# DanielDist_board_1_17.net
KiCad netlist of a schematic drawn in EAGLE
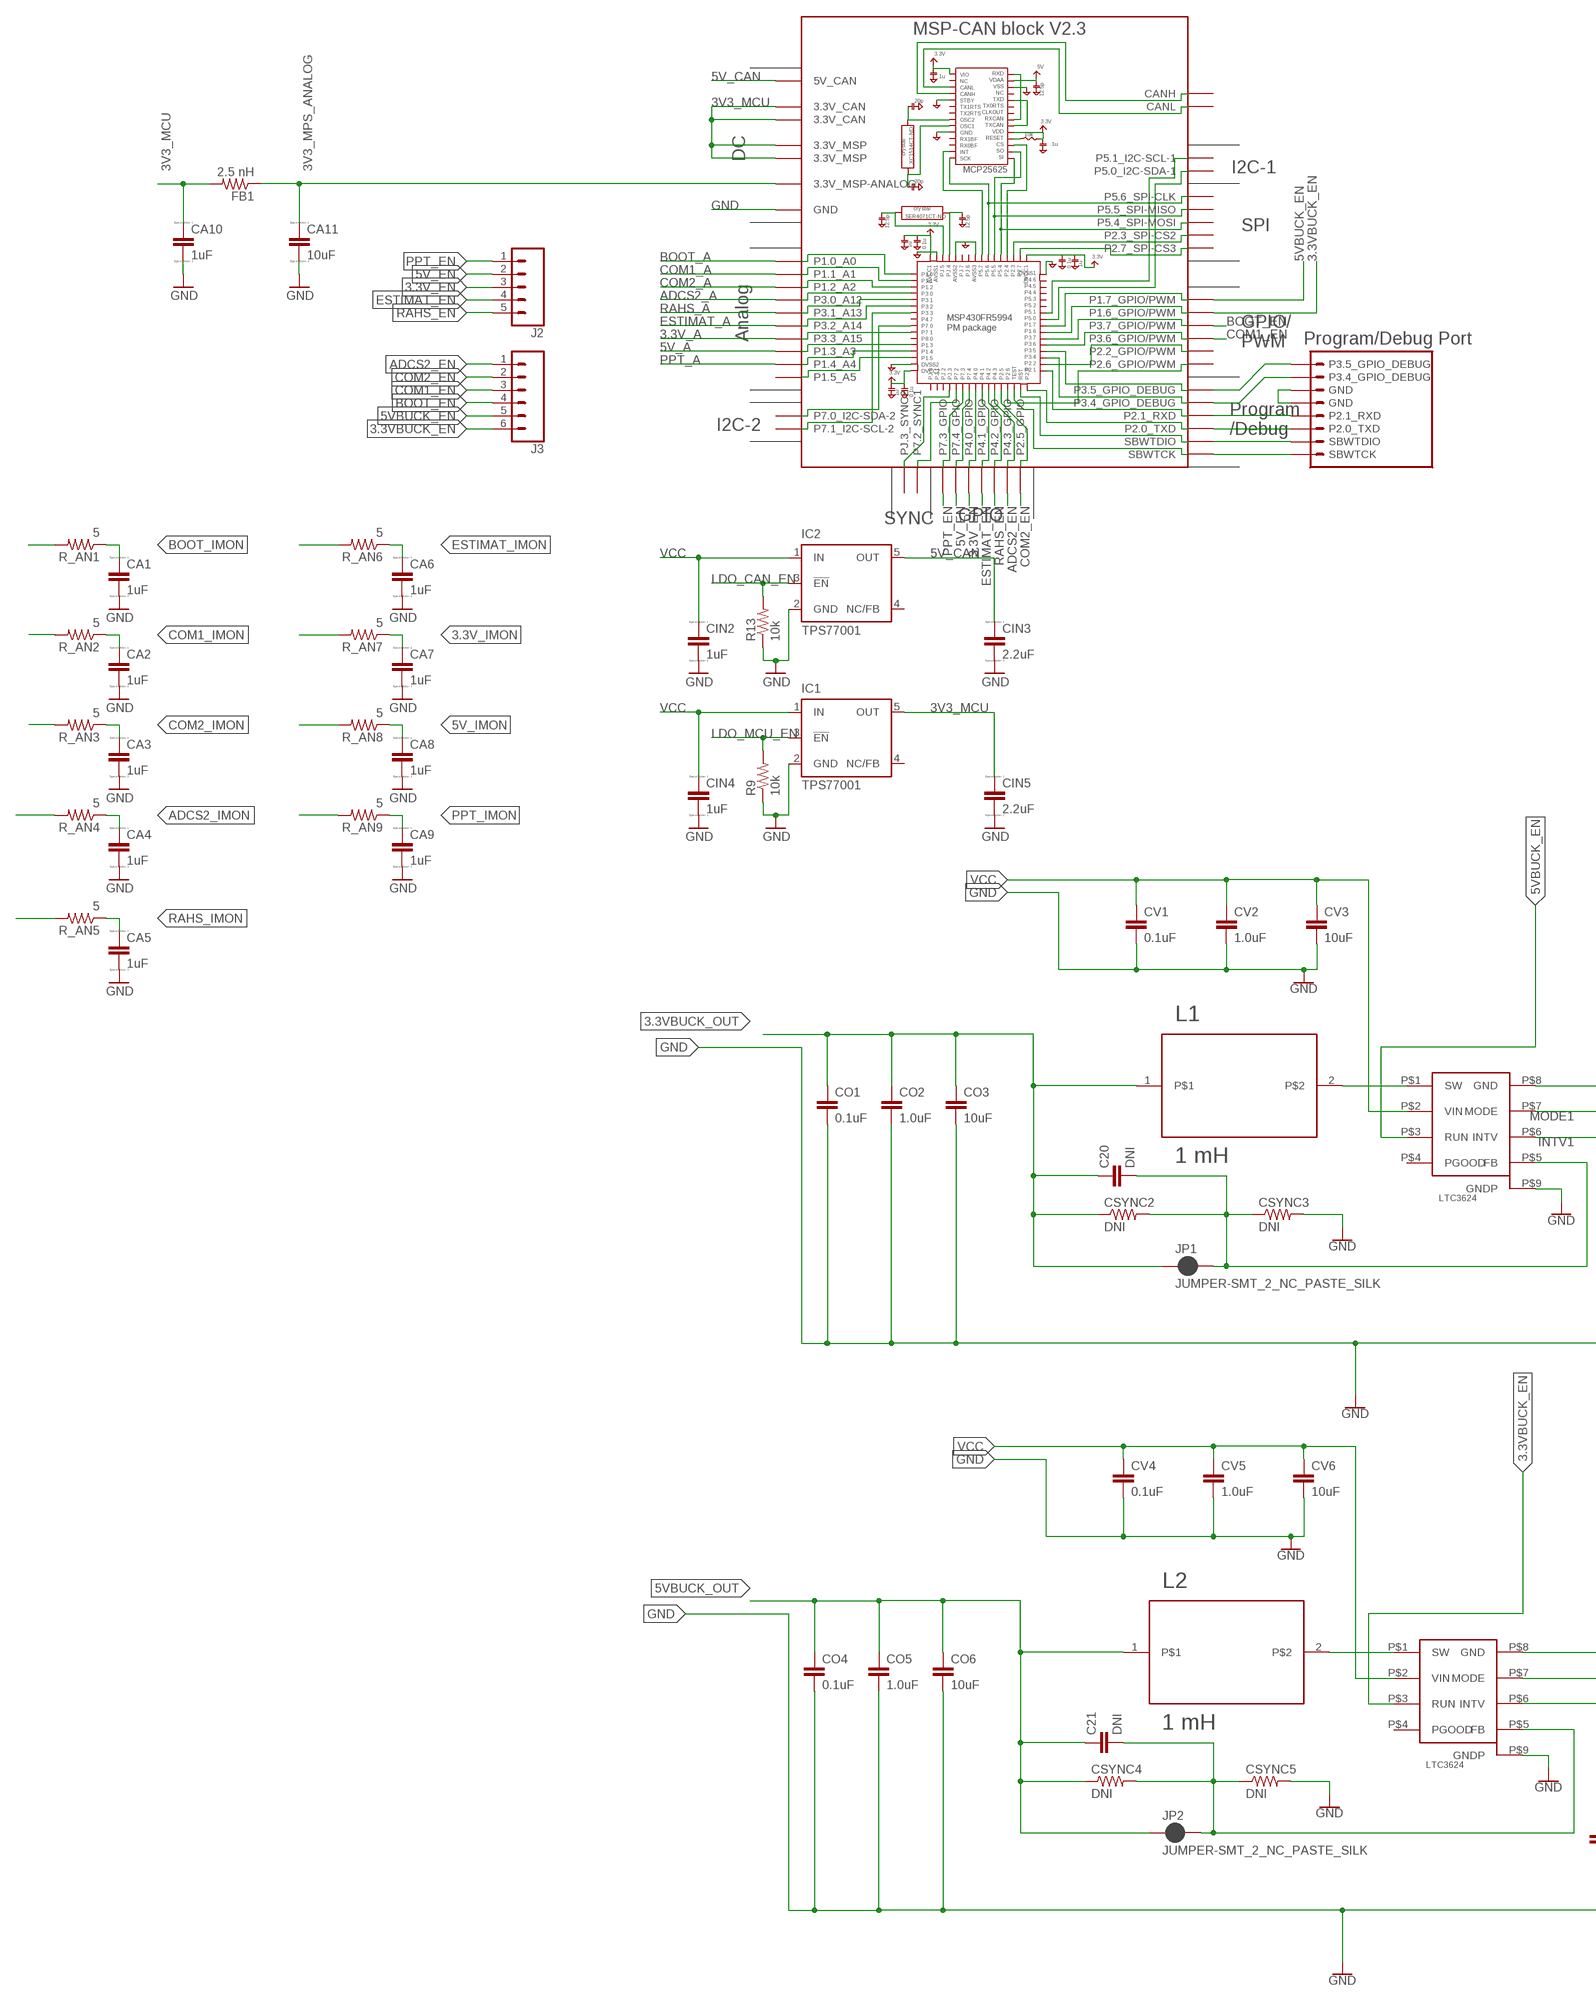
[diagram p0: schematic, sheet 1, part 1 of 3]
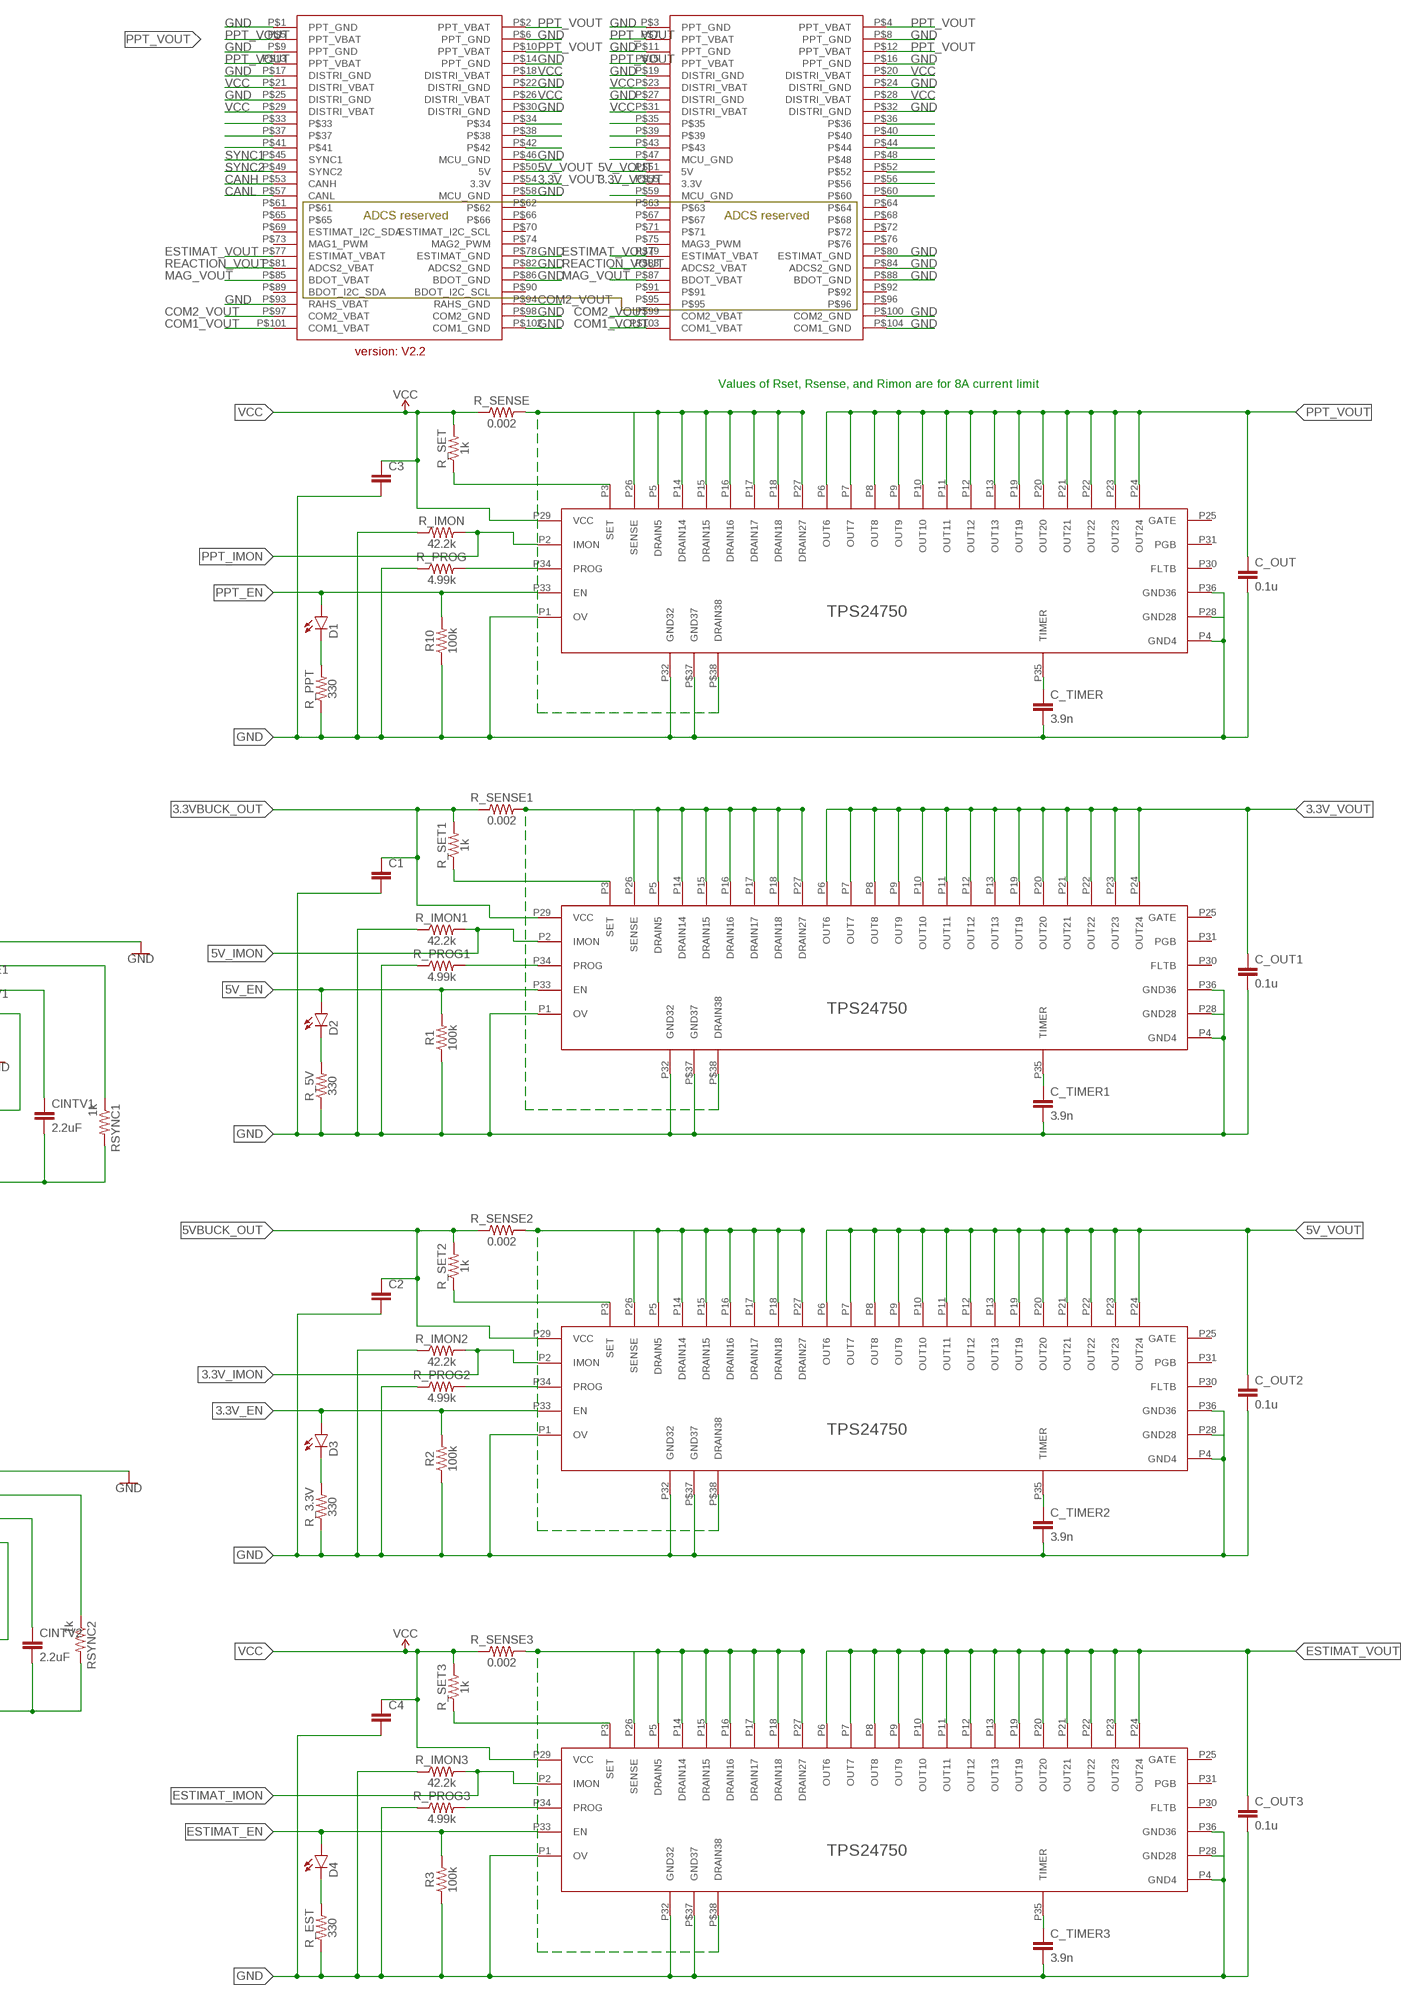
[diagram p1: schematic, sheet 1, part 2 of 3]
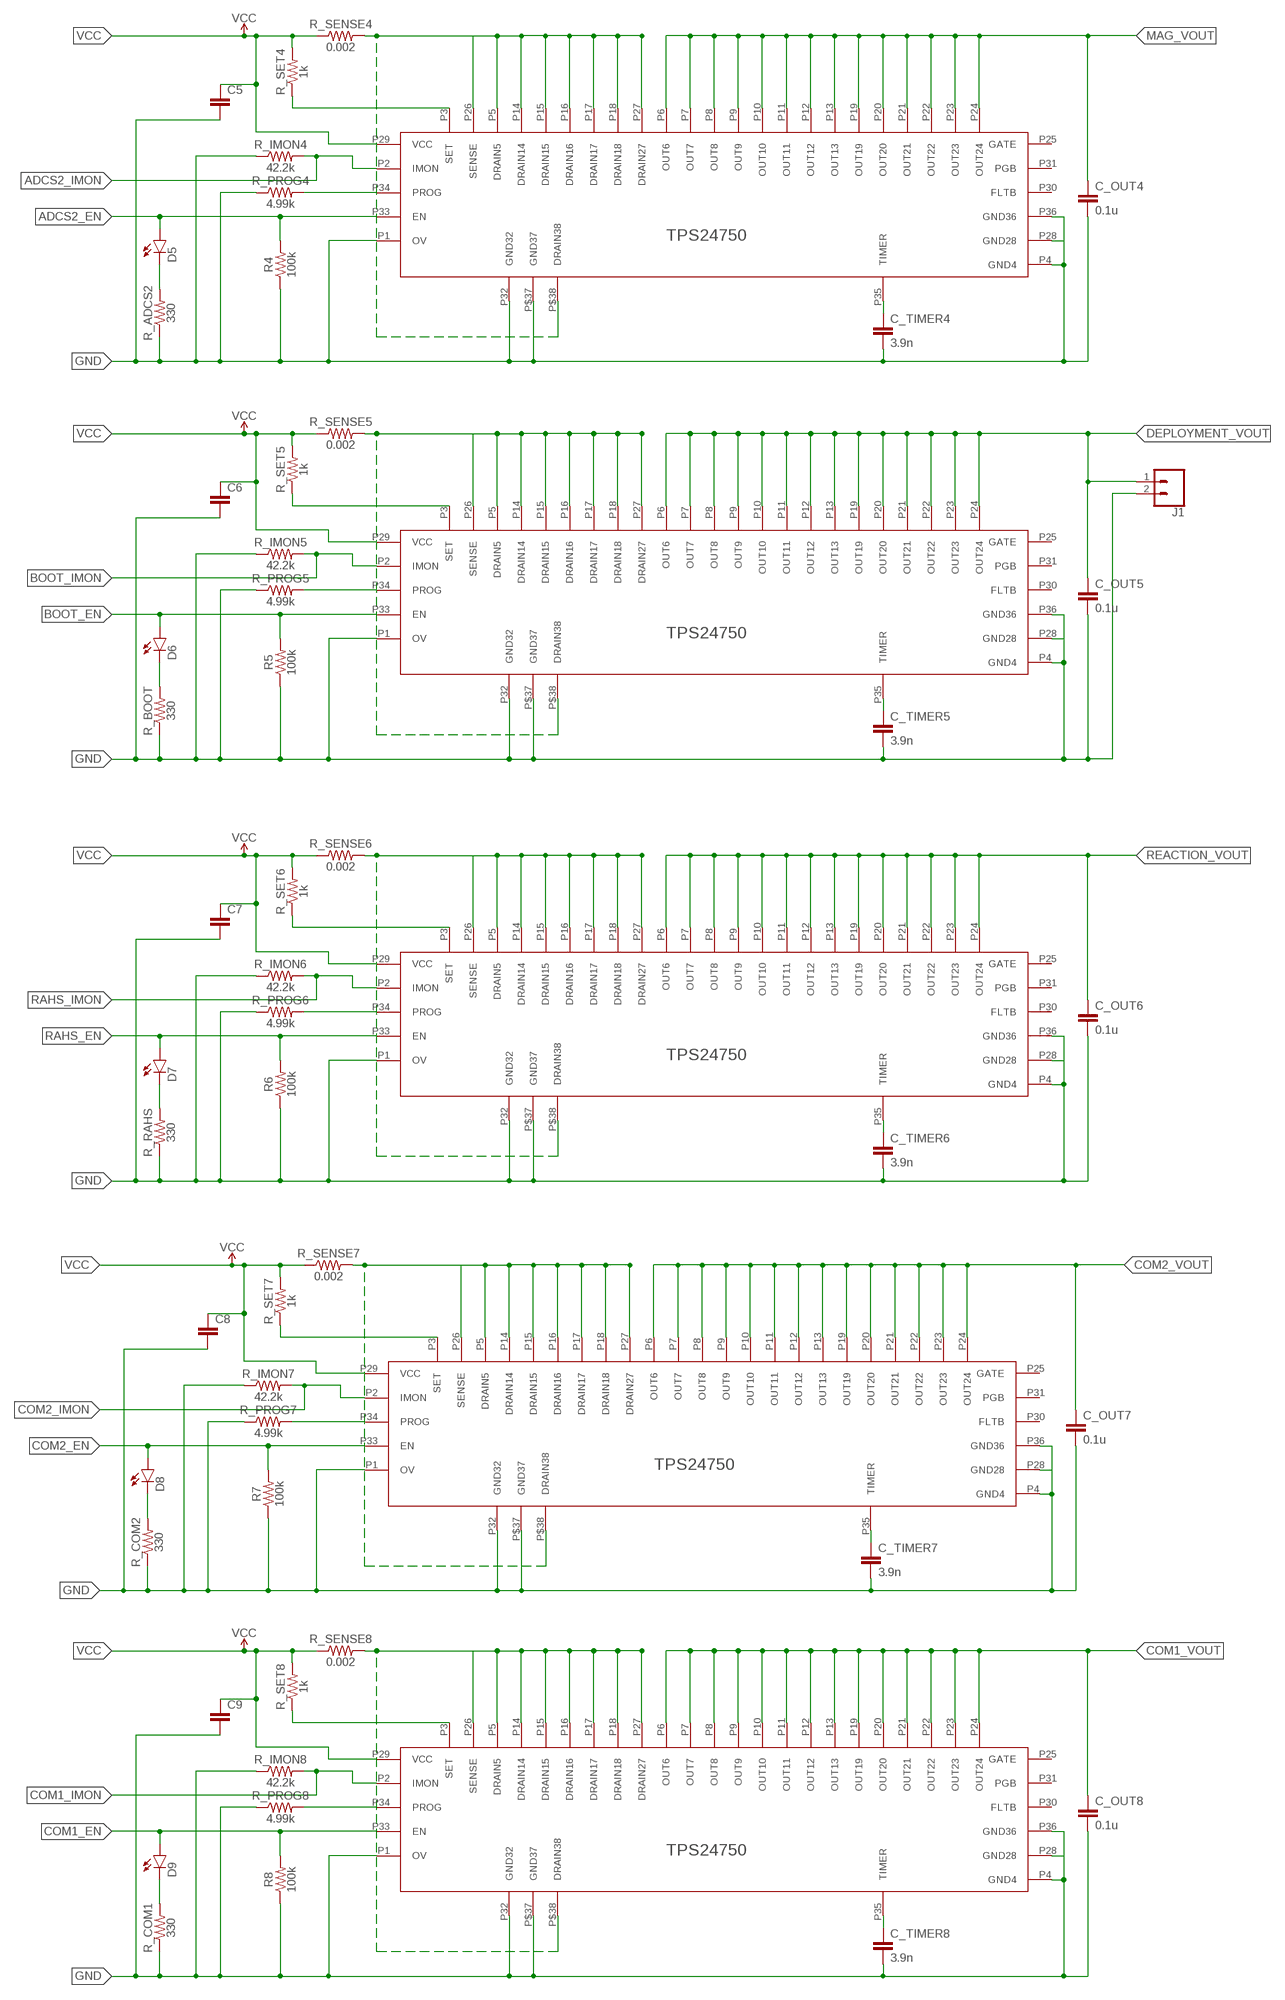
[diagram p2: schematic, sheet 1, part 3 of 3]

(export (version "E")
  (design (tool "Eeschema 10.0.6"))
  (components
    (comp (ref "C1")
      (value "GEN_CAP_0805SMD")
      (footprint "eagle-import:0805")
      (libsource (lib "eagle-import") (part "GEN_CAP_0805SMD"))
    )
    (comp (ref "C2")
      (value "GEN_CAP_0805SMD")
      (footprint "eagle-import:0805")
      (libsource (lib "eagle-import") (part "GEN_CAP_0805SMD"))
    )
    (comp (ref "C3")
      (value "GEN_CAP_0805SMD")
      (footprint "eagle-import:0805")
      (libsource (lib "eagle-import") (part "GEN_CAP_0805SMD"))
    )
    (comp (ref "C4")
      (value "GEN_CAP_0805SMD")
      (footprint "eagle-import:0805")
      (libsource (lib "eagle-import") (part "GEN_CAP_0805SMD"))
    )
    (comp (ref "C5")
      (value "GEN_CAP_0805SMD")
      (footprint "eagle-import:0805")
      (libsource (lib "eagle-import") (part "GEN_CAP_0805SMD"))
    )
    (comp (ref "C6")
      (value "GEN_CAP_0805SMD")
      (footprint "eagle-import:0805")
      (libsource (lib "eagle-import") (part "GEN_CAP_0805SMD"))
    )
    (comp (ref "C7")
      (value "GEN_CAP_0805SMD")
      (footprint "eagle-import:0805")
      (libsource (lib "eagle-import") (part "GEN_CAP_0805SMD"))
    )
    (comp (ref "C8")
      (value "GEN_CAP_0805SMD")
      (footprint "eagle-import:0805")
      (libsource (lib "eagle-import") (part "GEN_CAP_0805SMD"))
    )
    (comp (ref "C9")
      (value "GEN_CAP_0805SMD")
      (footprint "eagle-import:0805")
      (libsource (lib "eagle-import") (part "GEN_CAP_0805SMD"))
    )
    (comp (ref "C20")
      (value "DNI")
      (footprint "eagle-import:0805")
      (libsource (lib "eagle-import") (part "1.0UF-0805-25V-(+80/-20%)"))
    )
    (comp (ref "C21")
      (value "DNI")
      (footprint "eagle-import:0805")
      (libsource (lib "eagle-import") (part "1.0UF-0805-25V-(+80/-20%)"))
    )
    (comp (ref "CA1")
      (value "1uF")
      (footprint "eagle-import:C0805")
      (libsource (lib "eagle-import") (part "C"))
    )
    (comp (ref "CA2")
      (value "1uF")
      (footprint "eagle-import:C0805")
      (libsource (lib "eagle-import") (part "C"))
    )
    (comp (ref "CA3")
      (value "1uF")
      (footprint "eagle-import:C0805")
      (libsource (lib "eagle-import") (part "C"))
    )
    (comp (ref "CA4")
      (value "1uF")
      (footprint "eagle-import:C0805")
      (libsource (lib "eagle-import") (part "C"))
    )
    (comp (ref "CA5")
      (value "1uF")
      (footprint "eagle-import:C0805")
      (libsource (lib "eagle-import") (part "C"))
    )
    (comp (ref "CA6")
      (value "1uF")
      (footprint "eagle-import:C0805")
      (libsource (lib "eagle-import") (part "C"))
    )
    (comp (ref "CA7")
      (value "1uF")
      (footprint "eagle-import:C0805")
      (libsource (lib "eagle-import") (part "C"))
    )
    (comp (ref "CA8")
      (value "1uF")
      (footprint "eagle-import:C0805")
      (libsource (lib "eagle-import") (part "C"))
    )
    (comp (ref "CA9")
      (value "1uF")
      (footprint "eagle-import:C0805")
      (libsource (lib "eagle-import") (part "C"))
    )
    (comp (ref "CA10")
      (value "1uF")
      (footprint "eagle-import:C0805")
      (libsource (lib "eagle-import") (part "C"))
    )
    (comp (ref "CA11")
      (value "10uF")
      (footprint "eagle-import:C0805")
      (libsource (lib "eagle-import") (part "C"))
    )
    (comp (ref "CIN2")
      (value "1uF")
      (footprint "eagle-import:C0805")
      (libsource (lib "eagle-import") (part "C"))
    )
    (comp (ref "CIN3")
      (value "2.2uF")
      (footprint "eagle-import:C0805")
      (libsource (lib "eagle-import") (part "C"))
    )
    (comp (ref "CIN4")
      (value "1uF")
      (footprint "eagle-import:C0805")
      (libsource (lib "eagle-import") (part "C"))
    )
    (comp (ref "CIN5")
      (value "2.2uF")
      (footprint "eagle-import:C0805")
      (libsource (lib "eagle-import") (part "C"))
    )
    (comp (ref "CINTV1")
      (value "2.2uF")
      (footprint "eagle-import:0805")
      (libsource (lib "eagle-import") (part "2.2UF-0805-25V-(+80/-20%)"))
    )
    (comp (ref "CINTV2")
      (value "2.2uF")
      (footprint "eagle-import:0805")
      (libsource (lib "eagle-import") (part "2.2UF-0805-25V-(+80/-20%)"))
    )
    (comp (ref "CO1")
      (value "0.1uF")
      (footprint "eagle-import:0805")
      (libsource (lib "eagle-import") (part "1.0UF-0805-25V-(+80/-20%)"))
    )
    (comp (ref "CO2")
      (value "1.0uF")
      (footprint "eagle-import:0805")
      (libsource (lib "eagle-import") (part "1.0UF-0805-25V-(+80/-20%)"))
    )
    (comp (ref "CO3")
      (value "10uF")
      (footprint "eagle-import:0805")
      (libsource (lib "eagle-import") (part "10UF-0805-10V-10%"))
    )
    (comp (ref "CO4")
      (value "0.1uF")
      (footprint "eagle-import:0805")
      (libsource (lib "eagle-import") (part "1.0UF-0805-25V-(+80/-20%)"))
    )
    (comp (ref "CO5")
      (value "1.0uF")
      (footprint "eagle-import:0805")
      (libsource (lib "eagle-import") (part "1.0UF-0805-25V-(+80/-20%)"))
    )
    (comp (ref "CO6")
      (value "10uF")
      (footprint "eagle-import:0805")
      (libsource (lib "eagle-import") (part "10UF-0805-10V-10%"))
    )
    (comp (ref "CSYNC2")
      (value "DNI")
      (footprint "eagle-import:R0805")
      (libsource (lib "eagle-import") (part "R-US_R0805"))
    )
    (comp (ref "CSYNC3")
      (value "DNI")
      (footprint "eagle-import:R0805")
      (libsource (lib "eagle-import") (part "R-US_R0805"))
    )
    (comp (ref "CSYNC4")
      (value "DNI")
      (footprint "eagle-import:R0805")
      (libsource (lib "eagle-import") (part "R-US_R0805"))
    )
    (comp (ref "CSYNC5")
      (value "DNI")
      (footprint "eagle-import:R0805")
      (libsource (lib "eagle-import") (part "R-US_R0805"))
    )
    (comp (ref "CV1")
      (value "0.1uF")
      (footprint "eagle-import:0805")
      (libsource (lib "eagle-import") (part "1.0UF-0805-25V-10%"))
    )
    (comp (ref "CV2")
      (value "1.0uF")
      (footprint "eagle-import:0805")
      (libsource (lib "eagle-import") (part "1.0UF-0805-25V-10%"))
    )
    (comp (ref "CV3")
      (value "10uF")
      (footprint "eagle-import:0805")
      (libsource (lib "eagle-import") (part "1.0UF-0805-25V-10%"))
    )
    (comp (ref "CV4")
      (value "0.1uF")
      (footprint "eagle-import:0805")
      (libsource (lib "eagle-import") (part "1.0UF-0805-25V-10%"))
    )
    (comp (ref "CV5")
      (value "1.0uF")
      (footprint "eagle-import:0805")
      (libsource (lib "eagle-import") (part "1.0UF-0805-25V-10%"))
    )
    (comp (ref "CV6")
      (value "10uF")
      (footprint "eagle-import:0805")
      (libsource (lib "eagle-import") (part "1.0UF-0805-25V-10%"))
    )
    (comp (ref "C_OUT")
      (value "0.1u")
      (footprint "eagle-import:0805")
      (libsource (lib "eagle-import") (part "GEN_CAP_0805SMD"))
    )
    (comp (ref "C_OUT1")
      (value "0.1u")
      (footprint "eagle-import:0805")
      (libsource (lib "eagle-import") (part "GEN_CAP_0805SMD"))
    )
    (comp (ref "C_OUT2")
      (value "0.1u")
      (footprint "eagle-import:0805")
      (libsource (lib "eagle-import") (part "GEN_CAP_0805SMD"))
    )
    (comp (ref "C_OUT3")
      (value "0.1u")
      (footprint "eagle-import:0805")
      (libsource (lib "eagle-import") (part "GEN_CAP_0805SMD"))
    )
    (comp (ref "C_OUT4")
      (value "0.1u")
      (footprint "eagle-import:0805")
      (libsource (lib "eagle-import") (part "GEN_CAP_0805SMD"))
    )
    (comp (ref "C_OUT5")
      (value "0.1u")
      (footprint "eagle-import:0805")
      (libsource (lib "eagle-import") (part "GEN_CAP_0805SMD"))
    )
    (comp (ref "C_OUT6")
      (value "0.1u")
      (footprint "eagle-import:0805")
      (libsource (lib "eagle-import") (part "GEN_CAP_0805SMD"))
    )
    (comp (ref "C_OUT7")
      (value "0.1u")
      (footprint "eagle-import:0805")
      (libsource (lib "eagle-import") (part "GEN_CAP_0805SMD"))
    )
    (comp (ref "C_OUT8")
      (value "0.1u")
      (footprint "eagle-import:0805")
      (libsource (lib "eagle-import") (part "GEN_CAP_0805SMD"))
    )
    (comp (ref "C_TIMER")
      (value "3.9n")
      (footprint "eagle-import:0805")
      (libsource (lib "eagle-import") (part "GEN_CAP_0805SMD"))
    )
    (comp (ref "C_TIMER1")
      (value "3.9n")
      (footprint "eagle-import:0805")
      (libsource (lib "eagle-import") (part "GEN_CAP_0805SMD"))
    )
    (comp (ref "C_TIMER2")
      (value "3.9n")
      (footprint "eagle-import:0805")
      (libsource (lib "eagle-import") (part "GEN_CAP_0805SMD"))
    )
    (comp (ref "C_TIMER3")
      (value "3.9n")
      (footprint "eagle-import:0805")
      (libsource (lib "eagle-import") (part "GEN_CAP_0805SMD"))
    )
    (comp (ref "C_TIMER4")
      (value "3.9n")
      (footprint "eagle-import:0805")
      (libsource (lib "eagle-import") (part "GEN_CAP_0805SMD"))
    )
    (comp (ref "C_TIMER5")
      (value "3.9n")
      (footprint "eagle-import:0805")
      (libsource (lib "eagle-import") (part "GEN_CAP_0805SMD"))
    )
    (comp (ref "C_TIMER6")
      (value "3.9n")
      (footprint "eagle-import:0805")
      (libsource (lib "eagle-import") (part "GEN_CAP_0805SMD"))
    )
    (comp (ref "C_TIMER7")
      (value "3.9n")
      (footprint "eagle-import:0805")
      (libsource (lib "eagle-import") (part "GEN_CAP_0805SMD"))
    )
    (comp (ref "C_TIMER8")
      (value "3.9n")
      (footprint "eagle-import:0805")
      (libsource (lib "eagle-import") (part "GEN_CAP_0805SMD"))
    )
    (comp (ref "D1")
      (value "LED")
      (footprint "eagle-import:LED-1206")
      (libsource (lib "eagle-import") (part "LED"))
    )
    (comp (ref "D2")
      (value "LED")
      (footprint "eagle-import:LED-1206")
      (libsource (lib "eagle-import") (part "LED"))
    )
    (comp (ref "D3")
      (value "LED")
      (footprint "eagle-import:LED-1206")
      (libsource (lib "eagle-import") (part "LED"))
    )
    (comp (ref "D4")
      (value "LED")
      (footprint "eagle-import:LED-1206")
      (libsource (lib "eagle-import") (part "LED"))
    )
    (comp (ref "D5")
      (value "LED")
      (footprint "eagle-import:LED-1206")
      (libsource (lib "eagle-import") (part "LED"))
    )
    (comp (ref "D6")
      (value "LED")
      (footprint "eagle-import:LED-1206")
      (libsource (lib "eagle-import") (part "LED"))
    )
    (comp (ref "D7")
      (value "LED")
      (footprint "eagle-import:LED-1206")
      (libsource (lib "eagle-import") (part "LED"))
    )
    (comp (ref "D8")
      (value "LED")
      (footprint "eagle-import:LED-1206")
      (libsource (lib "eagle-import") (part "LED"))
    )
    (comp (ref "D9")
      (value "LED")
      (footprint "eagle-import:LED-1206")
      (libsource (lib "eagle-import") (part "LED"))
    )
    (comp (ref "FB1")
      (value "2.5 nH")
      (footprint "eagle-import:R0805")
      (libsource (lib "eagle-import") (part "R-US_R0805"))
    )
    (comp (ref "IC1")
      (value "TPS77001")
      (footprint "eagle-import:SOT23-DBV")
      (fields (field (name "MF") "TEXAS INSTRUMENTS") (field (name "MPN") "TPS77001DBVT"))
      (libsource (lib "eagle-import") (part "TPS77001"))
    )
    (comp (ref "IC2")
      (value "TPS77001")
      (footprint "eagle-import:SOT23-DBV")
      (fields (field (name "MF") "TEXAS INSTRUMENTS") (field (name "MPN") "TPS77001DBVT"))
      (libsource (lib "eagle-import") (part "TPS77001"))
    )
    (comp (ref "J1")
      (value "CONN_023.5MM")
      (footprint "eagle-import:SCREWTERMINAL-3.5MM-2")
      (libsource (lib "eagle-import") (part "CONN_023.5MM"))
    )
    (comp (ref "J2")
      (value "CONN_05LOCK")
      (footprint "eagle-import:1X05_LOCK")
      (libsource (lib "eagle-import") (part "CONN_05LOCK"))
    )
    (comp (ref "J3")
      (value "CONN_06LOCK")
      (footprint "eagle-import:1X06_LOCK")
      (libsource (lib "eagle-import") (part "CONN_06LOCK"))
    )
    (comp (ref "JP1")
      (value "JUMPER-SMT_2_NC_PASTE_SILK")
      (footprint "eagle-import:SMT-JUMPER_2_NC_PASTE_SILK")
      (libsource (lib "eagle-import") (part "JUMPER-SMT_2_NC_PASTE_SILK"))
    )
    (comp (ref "JP2")
      (value "JUMPER-SMT_2_NC_PASTE_SILK")
      (footprint "eagle-import:SMT-JUMPER_2_NC_PASTE_SILK")
      (libsource (lib "eagle-import") (part "JUMPER-SMT_2_NC_PASTE_SILK"))
    )
    (comp (ref "L1")
      (value "1 mH")
      (footprint "eagle-import:COILCRAFT")
      (libsource (lib "eagle-import") (part "XAL4030-332ME"))
    )
    (comp (ref "L2")
      (value "1 mH")
      (footprint "eagle-import:COILCRAFT")
      (libsource (lib "eagle-import") (part "XAL4030-332ME"))
    )
    (comp (ref "R1")
      (value "100k")
      (footprint "eagle-import:0805")
      (libsource (lib "eagle-import") (part "GEN_RES_0805SMD"))
    )
    (comp (ref "R2")
      (value "100k")
      (footprint "eagle-import:0805")
      (libsource (lib "eagle-import") (part "GEN_RES_0805SMD"))
    )
    (comp (ref "R3")
      (value "100k")
      (footprint "eagle-import:0805")
      (libsource (lib "eagle-import") (part "GEN_RES_0805SMD"))
    )
    (comp (ref "R4")
      (value "100k")
      (footprint "eagle-import:0805")
      (libsource (lib "eagle-import") (part "GEN_RES_0805SMD"))
    )
    (comp (ref "R5")
      (value "100k")
      (footprint "eagle-import:0805")
      (libsource (lib "eagle-import") (part "GEN_RES_0805SMD"))
    )
    (comp (ref "R6")
      (value "100k")
      (footprint "eagle-import:0805")
      (libsource (lib "eagle-import") (part "GEN_RES_0805SMD"))
    )
    (comp (ref "R7")
      (value "100k")
      (footprint "eagle-import:0805")
      (libsource (lib "eagle-import") (part "GEN_RES_0805SMD"))
    )
    (comp (ref "R8")
      (value "100k")
      (footprint "eagle-import:0805")
      (libsource (lib "eagle-import") (part "GEN_RES_0805SMD"))
    )
    (comp (ref "R9")
      (value "10k")
      (footprint "eagle-import:R0805")
      (libsource (lib "eagle-import") (part "R-US_R0805"))
    )
    (comp (ref "R10")
      (value "100k")
      (footprint "eagle-import:0805")
      (libsource (lib "eagle-import") (part "GEN_RES_0805SMD"))
    )
    (comp (ref "R13")
      (value "10k")
      (footprint "eagle-import:R0805")
      (libsource (lib "eagle-import") (part "R-US_R0805"))
    )
    (comp (ref "RSYNC1")
      (value "1k")
      (footprint "eagle-import:R0805")
      (libsource (lib "eagle-import") (part "R-US_R0805"))
    )
    (comp (ref "RSYNC2")
      (value "1k")
      (footprint "eagle-import:R0805")
      (libsource (lib "eagle-import") (part "R-US_R0805"))
    )
    (comp (ref "R_3.3V")
      (value "330")
      (footprint "eagle-import:0805")
      (libsource (lib "eagle-import") (part "GEN_RES_0805SMD"))
    )
    (comp (ref "R_5V")
      (value "330")
      (footprint "eagle-import:0805")
      (libsource (lib "eagle-import") (part "GEN_RES_0805SMD"))
    )
    (comp (ref "R_ADCS2")
      (value "330")
      (footprint "eagle-import:0805")
      (libsource (lib "eagle-import") (part "GEN_RES_0805SMD"))
    )
    (comp (ref "R_AN1")
      (value "5")
      (footprint "eagle-import:R0805")
      (libsource (lib "eagle-import") (part "R-US_R0805"))
    )
    (comp (ref "R_AN2")
      (value "5")
      (footprint "eagle-import:R0805")
      (libsource (lib "eagle-import") (part "R-US_R0805"))
    )
    (comp (ref "R_AN3")
      (value "5")
      (footprint "eagle-import:R0805")
      (libsource (lib "eagle-import") (part "R-US_R0805"))
    )
    (comp (ref "R_AN4")
      (value "5")
      (footprint "eagle-import:R0805")
      (libsource (lib "eagle-import") (part "R-US_R0805"))
    )
    (comp (ref "R_AN5")
      (value "5")
      (footprint "eagle-import:R0805")
      (libsource (lib "eagle-import") (part "R-US_R0805"))
    )
    (comp (ref "R_AN6")
      (value "5")
      (footprint "eagle-import:R0805")
      (libsource (lib "eagle-import") (part "R-US_R0805"))
    )
    (comp (ref "R_AN7")
      (value "5")
      (footprint "eagle-import:R0805")
      (libsource (lib "eagle-import") (part "R-US_R0805"))
    )
    (comp (ref "R_AN8")
      (value "5")
      (footprint "eagle-import:R0805")
      (libsource (lib "eagle-import") (part "R-US_R0805"))
    )
    (comp (ref "R_AN9")
      (value "5")
      (footprint "eagle-import:R0805")
      (libsource (lib "eagle-import") (part "R-US_R0805"))
    )
    (comp (ref "R_BOOT")
      (value "330")
      (footprint "eagle-import:0805")
      (libsource (lib "eagle-import") (part "GEN_RES_0805SMD"))
    )
    (comp (ref "R_COM1")
      (value "330")
      (footprint "eagle-import:0805")
      (libsource (lib "eagle-import") (part "GEN_RES_0805SMD"))
    )
    (comp (ref "R_COM2")
      (value "330")
      (footprint "eagle-import:0805")
      (libsource (lib "eagle-import") (part "GEN_RES_0805SMD"))
    )
    (comp (ref "R_EST")
      (value "330")
      (footprint "eagle-import:0805")
      (libsource (lib "eagle-import") (part "GEN_RES_0805SMD"))
    )
    (comp (ref "R_IMON")
      (value "42.2k")
      (footprint "eagle-import:0805")
      (libsource (lib "eagle-import") (part "GEN_RES_0805SMD"))
    )
    (comp (ref "R_IMON1")
      (value "42.2k")
      (footprint "eagle-import:0805")
      (libsource (lib "eagle-import") (part "GEN_RES_0805SMD"))
    )
    (comp (ref "R_IMON2")
      (value "42.2k")
      (footprint "eagle-import:0805")
      (libsource (lib "eagle-import") (part "GEN_RES_0805SMD"))
    )
    (comp (ref "R_IMON3")
      (value "42.2k")
      (footprint "eagle-import:0805")
      (libsource (lib "eagle-import") (part "GEN_RES_0805SMD"))
    )
    (comp (ref "R_IMON4")
      (value "42.2k")
      (footprint "eagle-import:0805")
      (libsource (lib "eagle-import") (part "GEN_RES_0805SMD"))
    )
    (comp (ref "R_IMON5")
      (value "42.2k")
      (footprint "eagle-import:0805")
      (libsource (lib "eagle-import") (part "GEN_RES_0805SMD"))
    )
    (comp (ref "R_IMON6")
      (value "42.2k")
      (footprint "eagle-import:0805")
      (libsource (lib "eagle-import") (part "GEN_RES_0805SMD"))
    )
    (comp (ref "R_IMON7")
      (value "42.2k")
      (footprint "eagle-import:0805")
      (libsource (lib "eagle-import") (part "GEN_RES_0805SMD"))
    )
    (comp (ref "R_IMON8")
      (value "42.2k")
      (footprint "eagle-import:0805")
      (libsource (lib "eagle-import") (part "GEN_RES_0805SMD"))
    )
    (comp (ref "R_PPT")
      (value "330")
      (footprint "eagle-import:0805")
      (libsource (lib "eagle-import") (part "GEN_RES_0805SMD"))
    )
    (comp (ref "R_PROG")
      (value "4.99k")
      (footprint "eagle-import:0805")
      (libsource (lib "eagle-import") (part "GEN_RES_0805SMD"))
    )
    (comp (ref "R_PROG1")
      (value "4.99k")
      (footprint "eagle-import:0805")
      (libsource (lib "eagle-import") (part "GEN_RES_0805SMD"))
    )
    (comp (ref "R_PROG2")
      (value "4.99k")
      (footprint "eagle-import:0805")
      (libsource (lib "eagle-import") (part "GEN_RES_0805SMD"))
    )
    (comp (ref "R_PROG3")
      (value "4.99k")
      (footprint "eagle-import:0805")
      (libsource (lib "eagle-import") (part "GEN_RES_0805SMD"))
    )
    (comp (ref "R_PROG4")
      (value "4.99k")
      (footprint "eagle-import:0805")
      (libsource (lib "eagle-import") (part "GEN_RES_0805SMD"))
    )
    (comp (ref "R_PROG5")
      (value "4.99k")
      (footprint "eagle-import:0805")
      (libsource (lib "eagle-import") (part "GEN_RES_0805SMD"))
    )
    (comp (ref "R_PROG6")
      (value "4.99k")
      (footprint "eagle-import:0805")
      (libsource (lib "eagle-import") (part "GEN_RES_0805SMD"))
    )
    (comp (ref "R_PROG7")
      (value "4.99k")
      (footprint "eagle-import:0805")
      (libsource (lib "eagle-import") (part "GEN_RES_0805SMD"))
    )
    (comp (ref "R_PROG8")
      (value "4.99k")
      (footprint "eagle-import:0805")
      (libsource (lib "eagle-import") (part "GEN_RES_0805SMD"))
    )
    (comp (ref "R_RAHS")
      (value "330")
      (footprint "eagle-import:0805")
      (libsource (lib "eagle-import") (part "GEN_RES_0805SMD"))
    )
    (comp (ref "R_SENSE")
      (value "0.002")
      (footprint "eagle-import:2010")
      (libsource (lib "eagle-import") (part "GEN_RES_2010SMD"))
    )
    (comp (ref "R_SENSE1")
      (value "0.002")
      (footprint "eagle-import:2010")
      (libsource (lib "eagle-import") (part "GEN_RES_2010SMD"))
    )
    (comp (ref "R_SENSE2")
      (value "0.002")
      (footprint "eagle-import:2010")
      (libsource (lib "eagle-import") (part "GEN_RES_2010SMD"))
    )
    (comp (ref "R_SENSE3")
      (value "0.002")
      (footprint "eagle-import:2010")
      (libsource (lib "eagle-import") (part "GEN_RES_2010SMD"))
    )
    (comp (ref "R_SENSE4")
      (value "0.002")
      (footprint "eagle-import:2010")
      (libsource (lib "eagle-import") (part "GEN_RES_2010SMD"))
    )
    (comp (ref "R_SENSE5")
      (value "0.002")
      (footprint "eagle-import:2010")
      (libsource (lib "eagle-import") (part "GEN_RES_2010SMD"))
    )
    (comp (ref "R_SENSE6")
      (value "0.002")
      (footprint "eagle-import:2010")
      (libsource (lib "eagle-import") (part "GEN_RES_2010SMD"))
    )
    (comp (ref "R_SENSE7")
      (value "0.002")
      (footprint "eagle-import:2010")
      (libsource (lib "eagle-import") (part "GEN_RES_2010SMD"))
    )
    (comp (ref "R_SENSE8")
      (value "0.002")
      (footprint "eagle-import:2010")
      (libsource (lib "eagle-import") (part "GEN_RES_2010SMD"))
    )
    (comp (ref "R_SET")
      (value "1k")
      (footprint "eagle-import:0805")
      (libsource (lib "eagle-import") (part "GEN_RES_0805SMD"))
    )
    (comp (ref "R_SET1")
      (value "1k")
      (footprint "eagle-import:0805")
      (libsource (lib "eagle-import") (part "GEN_RES_0805SMD"))
    )
    (comp (ref "R_SET2")
      (value "1k")
      (footprint "eagle-import:0805")
      (libsource (lib "eagle-import") (part "GEN_RES_0805SMD"))
    )
    (comp (ref "R_SET3")
      (value "1k")
      (footprint "eagle-import:0805")
      (libsource (lib "eagle-import") (part "GEN_RES_0805SMD"))
    )
    (comp (ref "R_SET4")
      (value "1k")
      (footprint "eagle-import:0805")
      (libsource (lib "eagle-import") (part "GEN_RES_0805SMD"))
    )
    (comp (ref "R_SET5")
      (value "1k")
      (footprint "eagle-import:0805")
      (libsource (lib "eagle-import") (part "GEN_RES_0805SMD"))
    )
    (comp (ref "R_SET6")
      (value "1k")
      (footprint "eagle-import:0805")
      (libsource (lib "eagle-import") (part "GEN_RES_0805SMD"))
    )
    (comp (ref "R_SET7")
      (value "1k")
      (footprint "eagle-import:0805")
      (libsource (lib "eagle-import") (part "GEN_RES_0805SMD"))
    )
    (comp (ref "R_SET8")
      (value "1k")
      (footprint "eagle-import:0805")
      (libsource (lib "eagle-import") (part "GEN_RES_0805SMD"))
    )
    (comp (ref "U$1")
      (value "TI_SWITCH_TPS24750")
      (footprint "eagle-import:QFN-36")
      (libsource (lib "eagle-import") (part "TI_SWITCH_TPS24750"))
    )
    (comp (ref "U$2")
      (value "PC104_CONNECTOR")
      (footprint "eagle-import:PC104_CONNECTOR")
      (libsource (lib "eagle-import") (part "PC104_CONNECTOR"))
    )
    (comp (ref "U$5")
      (value "TI_SWITCH_TPS24750")
      (footprint "eagle-import:QFN-36")
      (libsource (lib "eagle-import") (part "TI_SWITCH_TPS24750"))
    )
    (comp (ref "U$6")
      (value "TI_SWITCH_TPS24750")
      (footprint "eagle-import:QFN-36")
      (libsource (lib "eagle-import") (part "TI_SWITCH_TPS24750"))
    )
    (comp (ref "U$7")
      (value "TI_SWITCH_TPS24750")
      (footprint "eagle-import:QFN-36")
      (libsource (lib "eagle-import") (part "TI_SWITCH_TPS24750"))
    )
    (comp (ref "U$8")
      (value "TI_SWITCH_TPS24750")
      (footprint "eagle-import:QFN-36")
      (libsource (lib "eagle-import") (part "TI_SWITCH_TPS24750"))
    )
    (comp (ref "U$9")
      (value "TI_SWITCH_TPS24750")
      (footprint "eagle-import:QFN-36")
      (libsource (lib "eagle-import") (part "TI_SWITCH_TPS24750"))
    )
    (comp (ref "U$10")
      (value "TI_SWITCH_TPS24750")
      (footprint "eagle-import:QFN-36")
      (libsource (lib "eagle-import") (part "TI_SWITCH_TPS24750"))
    )
    (comp (ref "U$11")
      (value "TI_SWITCH_TPS24750")
      (footprint "eagle-import:QFN-36")
      (libsource (lib "eagle-import") (part "TI_SWITCH_TPS24750"))
    )
    (comp (ref "U$12")
      (value "TI_SWITCH_TPS24750")
      (footprint "eagle-import:QFN-36")
      (libsource (lib "eagle-import") (part "TI_SWITCH_TPS24750"))
    )
    (comp (ref "U$13")
      (value "LINEAR_BUCK_LTC3624")
      (footprint "eagle-import:8-LFCSP")
      (libsource (lib "eagle-import") (part "LINEAR_BUCK_LTC3624"))
    )
    (comp (ref "U$14")
      (value "LINEAR_BUCK_LTC3624")
      (footprint "eagle-import:8-LFCSP")
      (libsource (lib "eagle-import") (part "LINEAR_BUCK_LTC3624"))
    )
    (comp (ref "U$15")
      (value "MSP-CAN_BLOCK")
      (footprint "eagle-import:MSP-CAN_BLOCK")
      (libsource (lib "eagle-import") (part "MSP-CAN_BLOCK"))
    )
    (comp (ref "U$16")
      (value "PROGRAM/DEBUG_PORT")
      (footprint "eagle-import:1X08_CONNECTOR")
      (libsource (lib "eagle-import") (part "PROGRAM/DEBUG_PORT"))
    )
  )
  (nets
    (net (code "1") (name "/3.3V_A") (class "Default")
      (node (ref "CA7") (pin "1") (pinfunction "1_1") (pintype "passive"))
      (node (ref "R_AN7") (pin "1") (pinfunction "1_1") (pintype "passive"))
      (node (ref "U$15") (pin "P3.3_A15") (pinfunction "P3.3_A15_P3.3_A15") (pintype "bidirectional"))
    )
    (net (code "2") (name "/3V3_MCU") (class "Default")
      (node (ref "CA10") (pin "1") (pinfunction "1_1") (pintype "passive"))
      (node (ref "CIN5") (pin "1") (pinfunction "1_1") (pintype "passive"))
      (node (ref "FB1") (pin "2") (pinfunction "2_2") (pintype "passive"))
      (node (ref "IC1") (pin "5") (pinfunction "OUT_5") (pintype "passive"))
      (node (ref "U$15") (pin "3.3V@CAN1") (pinfunction "3.3V_CAN_3.3V@CAN1") (pintype "bidirectional"))
      (node (ref "U$15") (pin "3.3V@CAN2") (pinfunction "3.3V_CAN_3.3V@CAN2") (pintype "bidirectional"))
      (node (ref "U$15") (pin "3.3V@MSP1") (pinfunction "3.3V_MSP_3.3V@MSP1") (pintype "bidirectional"))
      (node (ref "U$15") (pin "3.3V@MSP2") (pinfunction "3.3V_MSP_3.3V@MSP2") (pintype "bidirectional"))
    )
    (net (code "3") (name "/3V3_MPS_ANALOG") (class "Default")
      (node (ref "CA11") (pin "1") (pinfunction "1_1") (pintype "passive"))
      (node (ref "FB1") (pin "1") (pinfunction "1_1") (pintype "passive"))
      (node (ref "U$15") (pin "3.3V_ANALOG@MSP2") (pinfunction "3.3V_MSP-ANALOG_3.3V_ANALOG@MSP2") (pintype "bidirectional"))
    )
    (net (code "4") (name "/5V_A") (class "Default")
      (node (ref "CA8") (pin "1") (pinfunction "1_1") (pintype "passive"))
      (node (ref "R_AN8") (pin "1") (pinfunction "1_1") (pintype "passive"))
      (node (ref "U$15") (pin "P1.3_A3") (pinfunction "P1.3_A3_P1.3_A3") (pintype "bidirectional"))
    )
    (net (code "5") (name "/5V_CAN") (class "Default")
      (node (ref "CIN3") (pin "1") (pinfunction "1_1") (pintype "passive"))
      (node (ref "IC2") (pin "5") (pinfunction "OUT_5") (pintype "passive"))
      (node (ref "U$15") (pin "5V") (pinfunction "5V_CAN_5V") (pintype "bidirectional"))
    )
    (net (code "6") (name "/ADCS2_A") (class "Default")
      (node (ref "CA4") (pin "1") (pinfunction "1_1") (pintype "passive"))
      (node (ref "R_AN4") (pin "1") (pinfunction "1_1") (pintype "passive"))
      (node (ref "U$15") (pin "P3.0_A12") (pinfunction "P3.0_A12_P3.0_A12") (pintype "bidirectional"))
    )
    (net (code "7") (name "/BOOT_A") (class "Default")
      (node (ref "CA1") (pin "1") (pinfunction "1_1") (pintype "passive"))
      (node (ref "R_AN1") (pin "1") (pinfunction "1_1") (pintype "passive"))
      (node (ref "U$15") (pin "P1.0_A0") (pinfunction "P1.0_A0_P1.0_A0") (pintype "bidirectional"))
    )
    (net (code "8") (name "/CANH") (class "Default")
      (node (ref "U$2") (pin "P$53") (pinfunction "CANH_P$53") (pintype "bidirectional"))
    )
    (net (code "9") (name "/CANL") (class "Default")
      (node (ref "U$2") (pin "P$57") (pinfunction "CANL_P$57") (pintype "bidirectional"))
    )
    (net (code "10") (name "/COM1_A") (class "Default")
      (node (ref "CA2") (pin "1") (pinfunction "1_1") (pintype "passive"))
      (node (ref "R_AN2") (pin "1") (pinfunction "1_1") (pintype "passive"))
      (node (ref "U$15") (pin "P1.1_A1") (pinfunction "P1.1_A1_P1.1_A1") (pintype "bidirectional"))
    )
    (net (code "11") (name "/COM2_A") (class "Default")
      (node (ref "CA3") (pin "1") (pinfunction "1_1") (pintype "passive"))
      (node (ref "R_AN3") (pin "1") (pinfunction "1_1") (pintype "passive"))
      (node (ref "U$15") (pin "P1.2_A2") (pinfunction "P1.2_A2_P1.2_A2") (pintype "bidirectional"))
    )
    (net (code "12") (name "/ESTIMAT_A") (class "Default")
      (node (ref "CA6") (pin "1") (pinfunction "1_1") (pintype "passive"))
      (node (ref "R_AN6") (pin "1") (pinfunction "1_1") (pintype "passive"))
      (node (ref "U$15") (pin "P3.2_A14") (pinfunction "P3.2_A14_P3.2_A14") (pintype "bidirectional"))
    )
    (net (code "13") (name "/INTV1") (class "Default")
      (node (ref "CINTV1") (pin "1") (pinfunction "1_1") (pintype "passive"))
      (node (ref "U$13") (pin "P$6") (pinfunction "INTV_P$6") (pintype "bidirectional"))
    )
    (net (code "14") (name "/LDO_CAN_EN") (class "Default")
      (node (ref "IC2") (pin "3") (pinfunction "~{EN}_3") (pintype "input"))
      (node (ref "R13") (pin "2") (pinfunction "2_2") (pintype "passive"))
    )
    (net (code "15") (name "/LDO_MCU_EN") (class "Default")
      (node (ref "IC1") (pin "3") (pinfunction "~{EN}_3") (pintype "input"))
      (node (ref "R9") (pin "2") (pinfunction "2_2") (pintype "passive"))
    )
    (net (code "16") (name "/MODE1") (class "Default")
      (node (ref "RSYNC1") (pin "1") (pinfunction "1_1") (pintype "passive"))
      (node (ref "U$13") (pin "P$7") (pinfunction "MODE_P$7") (pintype "bidirectional"))
    )
    (net (code "17") (name "/PPT_A") (class "Default")
      (node (ref "CA9") (pin "1") (pinfunction "1_1") (pintype "passive"))
      (node (ref "R_AN9") (pin "1") (pinfunction "1_1") (pintype "passive"))
      (node (ref "U$15") (pin "P1.4_A4") (pinfunction "P1.4_A4_P1.4_A4") (pintype "bidirectional"))
    )
    (net (code "18") (name "/RAHS_A") (class "Default")
      (node (ref "CA5") (pin "1") (pinfunction "1_1") (pintype "passive"))
      (node (ref "R_AN5") (pin "1") (pinfunction "1_1") (pintype "passive"))
      (node (ref "U$15") (pin "P3.1_A13") (pinfunction "P3.1_A13_P3.1_A13") (pintype "bidirectional"))
    )
    (net (code "19") (name "/SYNC1") (class "Default")
      (node (ref "U$2") (pin "P$45") (pinfunction "SYNC1_P$45") (pintype "bidirectional"))
    )
    (net (code "20") (name "/SYNC2") (class "Default")
      (node (ref "U$2") (pin "P$49") (pinfunction "SYNC2_P$49") (pintype "bidirectional"))
    )
    (net (code "21") (name "3.3VBUCK_EN") (class "Default")
      (node (ref "J3") (pin "6") (pinfunction "6_6") (pintype "passive"))
      (node (ref "U$14") (pin "P$3") (pinfunction "RUN_P$3") (pintype "bidirectional"))
      (node (ref "U$15") (pin "P1.6_GPIO/PWM") (pinfunction "P1.6_GPIO/PWM_P1.6_GPIO/PWM") (pintype "bidirectional"))
    )
    (net (code "22") (name "3.3VBUCK_OUT") (class "Default")
      (node (ref "C1") (pin "1") (pinfunction "1_1") (pintype "passive"))
      (node (ref "C20") (pin "1") (pinfunction "1_1") (pintype "passive"))
      (node (ref "CO1") (pin "1") (pinfunction "1_1") (pintype "passive"))
      (node (ref "CO2") (pin "1") (pinfunction "1_1") (pintype "passive"))
      (node (ref "CO3") (pin "1") (pinfunction "1_1") (pintype "passive"))
      (node (ref "CSYNC2") (pin "1") (pinfunction "1_1") (pintype "passive"))
      (node (ref "JP1") (pin "1") (pinfunction "1_1") (pintype "passive"))
      (node (ref "L1") (pin "1") (pinfunction "P$1_1") (pintype "bidirectional"))
      (node (ref "R_SENSE1") (pin "1") (pinfunction "1_1") (pintype "passive"))
      (node (ref "R_SET1") (pin "2") (pinfunction "2_2") (pintype "passive"))
      (node (ref "U$5") (pin "P29") (pinfunction "VCC_P29") (pintype "bidirectional"))
    )
    (net (code "23") (name "3.3V_EN") (class "Default")
      (node (ref "D3") (pin "A") (pinfunction "A_A") (pintype "passive"))
      (node (ref "J2") (pin "3") (pinfunction "3_3") (pintype "passive"))
      (node (ref "R2") (pin "2") (pinfunction "2_2") (pintype "passive"))
      (node (ref "U$15") (pin "P4.0_GPIO") (pinfunction "P4.0_GPIO_P4.0_GPIO") (pintype "bidirectional"))
      (node (ref "U$6") (pin "P33") (pinfunction "EN_P33") (pintype "bidirectional"))
    )
    (net (code "24") (name "3.3V_IMON") (class "Default")
      (node (ref "R_AN7") (pin "2") (pinfunction "2_2") (pintype "passive"))
      (node (ref "R_IMON2") (pin "2") (pinfunction "2_2") (pintype "passive"))
      (node (ref "U$6") (pin "P2") (pinfunction "IMON_P2") (pintype "bidirectional"))
    )
    (net (code "25") (name "3.3V_VOUT") (class "Default")
      (node (ref "C_OUT1") (pin "1") (pinfunction "1_1") (pintype "passive"))
      (node (ref "U$2") (pin "P$54") (pinfunction "3.3V_P$54") (pintype "bidirectional"))
      (node (ref "U$2") (pin "P$55") (pinfunction "3.3V_P$55") (pintype "bidirectional"))
      (node (ref "U$5") (pin "P10") (pinfunction "OUT10_P10") (pintype "bidirectional"))
      (node (ref "U$5") (pin "P11") (pinfunction "OUT11_P11") (pintype "bidirectional"))
      (node (ref "U$5") (pin "P12") (pinfunction "OUT12_P12") (pintype "bidirectional"))
      (node (ref "U$5") (pin "P13") (pinfunction "OUT13_P13") (pintype "bidirectional"))
      (node (ref "U$5") (pin "P19") (pinfunction "OUT19_P19") (pintype "bidirectional"))
      (node (ref "U$5") (pin "P20") (pinfunction "OUT20_P20") (pintype "bidirectional"))
      (node (ref "U$5") (pin "P21") (pinfunction "OUT21_P21") (pintype "bidirectional"))
      (node (ref "U$5") (pin "P22") (pinfunction "OUT22_P22") (pintype "bidirectional"))
      (node (ref "U$5") (pin "P23") (pinfunction "OUT23_P23") (pintype "bidirectional"))
      (node (ref "U$5") (pin "P24") (pinfunction "OUT24_P24") (pintype "bidirectional"))
      (node (ref "U$5") (pin "P6") (pinfunction "OUT6_P6") (pintype "bidirectional"))
      (node (ref "U$5") (pin "P7") (pinfunction "OUT7_P7") (pintype "bidirectional"))
      (node (ref "U$5") (pin "P8") (pinfunction "OUT8_P8") (pintype "bidirectional"))
      (node (ref "U$5") (pin "P9") (pinfunction "OUT9_P9") (pintype "bidirectional"))
    )
    (net (code "26") (name "5VBUCK_EN") (class "Default")
      (node (ref "J3") (pin "5") (pinfunction "5_5") (pintype "passive"))
      (node (ref "U$13") (pin "P$3") (pinfunction "RUN_P$3") (pintype "bidirectional"))
      (node (ref "U$15") (pin "P1.7_GPIO/PWM") (pinfunction "P1.7_GPIO/PWM_P1.7_GPIO/PWM") (pintype "bidirectional"))
    )
    (net (code "27") (name "5VBUCK_OUT") (class "Default")
      (node (ref "C2") (pin "1") (pinfunction "1_1") (pintype "passive"))
      (node (ref "C21") (pin "1") (pinfunction "1_1") (pintype "passive"))
      (node (ref "CO4") (pin "1") (pinfunction "1_1") (pintype "passive"))
      (node (ref "CO5") (pin "1") (pinfunction "1_1") (pintype "passive"))
      (node (ref "CO6") (pin "1") (pinfunction "1_1") (pintype "passive"))
      (node (ref "CSYNC4") (pin "1") (pinfunction "1_1") (pintype "passive"))
      (node (ref "JP2") (pin "1") (pinfunction "1_1") (pintype "passive"))
      (node (ref "L2") (pin "1") (pinfunction "P$1_1") (pintype "bidirectional"))
      (node (ref "R_SENSE2") (pin "1") (pinfunction "1_1") (pintype "passive"))
      (node (ref "R_SET2") (pin "2") (pinfunction "2_2") (pintype "passive"))
      (node (ref "U$6") (pin "P29") (pinfunction "VCC_P29") (pintype "bidirectional"))
    )
    (net (code "28") (name "5V_EN") (class "Default")
      (node (ref "D2") (pin "A") (pinfunction "A_A") (pintype "passive"))
      (node (ref "J2") (pin "2") (pinfunction "2_2") (pintype "passive"))
      (node (ref "R1") (pin "2") (pinfunction "2_2") (pintype "passive"))
      (node (ref "U$15") (pin "P7.4_GPIO") (pinfunction "P7.4_GPIO_P7.4_GPIO") (pintype "bidirectional"))
      (node (ref "U$5") (pin "P33") (pinfunction "EN_P33") (pintype "bidirectional"))
    )
    (net (code "29") (name "5V_IMON") (class "Default")
      (node (ref "R_AN8") (pin "2") (pinfunction "2_2") (pintype "passive"))
      (node (ref "R_IMON1") (pin "2") (pinfunction "2_2") (pintype "passive"))
      (node (ref "U$5") (pin "P2") (pinfunction "IMON_P2") (pintype "bidirectional"))
    )
    (net (code "30") (name "5V_VOUT") (class "Default")
      (node (ref "C_OUT2") (pin "1") (pinfunction "1_1") (pintype "passive"))
      (node (ref "U$2") (pin "P$50") (pinfunction "5V_P$50") (pintype "bidirectional"))
      (node (ref "U$2") (pin "P$51") (pinfunction "5V_P$51") (pintype "bidirectional"))
      (node (ref "U$6") (pin "P10") (pinfunction "OUT10_P10") (pintype "bidirectional"))
      (node (ref "U$6") (pin "P11") (pinfunction "OUT11_P11") (pintype "bidirectional"))
      (node (ref "U$6") (pin "P12") (pinfunction "OUT12_P12") (pintype "bidirectional"))
      (node (ref "U$6") (pin "P13") (pinfunction "OUT13_P13") (pintype "bidirectional"))
      (node (ref "U$6") (pin "P19") (pinfunction "OUT19_P19") (pintype "bidirectional"))
      (node (ref "U$6") (pin "P20") (pinfunction "OUT20_P20") (pintype "bidirectional"))
      (node (ref "U$6") (pin "P21") (pinfunction "OUT21_P21") (pintype "bidirectional"))
      (node (ref "U$6") (pin "P22") (pinfunction "OUT22_P22") (pintype "bidirectional"))
      (node (ref "U$6") (pin "P23") (pinfunction "OUT23_P23") (pintype "bidirectional"))
      (node (ref "U$6") (pin "P24") (pinfunction "OUT24_P24") (pintype "bidirectional"))
      (node (ref "U$6") (pin "P6") (pinfunction "OUT6_P6") (pintype "bidirectional"))
      (node (ref "U$6") (pin "P7") (pinfunction "OUT7_P7") (pintype "bidirectional"))
      (node (ref "U$6") (pin "P8") (pinfunction "OUT8_P8") (pintype "bidirectional"))
      (node (ref "U$6") (pin "P9") (pinfunction "OUT9_P9") (pintype "bidirectional"))
    )
    (net (code "31") (name "ADCS2_EN") (class "Default")
      (node (ref "D5") (pin "A") (pinfunction "A_A") (pintype "passive"))
      (node (ref "J3") (pin "1") (pinfunction "1_1") (pintype "passive"))
      (node (ref "R4") (pin "2") (pinfunction "2_2") (pintype "passive"))
      (node (ref "U$15") (pin "P4.3_GPIO") (pinfunction "P4.3_GPIO_P4.3_GPIO") (pintype "bidirectional"))
      (node (ref "U$8") (pin "P33") (pinfunction "EN_P33") (pintype "bidirectional"))
    )
    (net (code "32") (name "ADCS2_IMON") (class "Default")
      (node (ref "R_AN4") (pin "2") (pinfunction "2_2") (pintype "passive"))
      (node (ref "R_IMON4") (pin "2") (pinfunction "2_2") (pintype "passive"))
      (node (ref "U$8") (pin "P2") (pinfunction "IMON_P2") (pintype "bidirectional"))
    )
    (net (code "33") (name "BOOT_EN") (class "Default")
      (node (ref "D6") (pin "A") (pinfunction "A_A") (pintype "passive"))
      (node (ref "J3") (pin "4") (pinfunction "4_4") (pintype "passive"))
      (node (ref "R5") (pin "2") (pinfunction "2_2") (pintype "passive"))
      (node (ref "U$15") (pin "P3.7_GPIO/PWM") (pinfunction "P3.7_GPIO/PWM_P3.7_GPIO/PWM") (pintype "bidirectional"))
      (node (ref "U$9") (pin "P33") (pinfunction "EN_P33") (pintype "bidirectional"))
    )
    (net (code "34") (name "BOOT_IMON") (class "Default")
      (node (ref "R_AN1") (pin "2") (pinfunction "2_2") (pintype "passive"))
      (node (ref "R_IMON5") (pin "2") (pinfunction "2_2") (pintype "passive"))
      (node (ref "U$9") (pin "P2") (pinfunction "IMON_P2") (pintype "bidirectional"))
    )
    (net (code "35") (name "COM1_EN") (class "Default")
      (node (ref "D9") (pin "A") (pinfunction "A_A") (pintype "passive"))
      (node (ref "J3") (pin "3") (pinfunction "3_3") (pintype "passive"))
      (node (ref "R8") (pin "2") (pinfunction "2_2") (pintype "passive"))
      (node (ref "U$12") (pin "P33") (pinfunction "EN_P33") (pintype "bidirectional"))
      (node (ref "U$15") (pin "P3.6_GPIO/PWM") (pinfunction "P3.6_GPIO/PWM_P3.6_GPIO/PWM") (pintype "bidirectional"))
    )
    (net (code "36") (name "COM1_IMON") (class "Default")
      (node (ref "R_AN2") (pin "2") (pinfunction "2_2") (pintype "passive"))
      (node (ref "R_IMON8") (pin "2") (pinfunction "2_2") (pintype "passive"))
      (node (ref "U$12") (pin "P2") (pinfunction "IMON_P2") (pintype "bidirectional"))
    )
    (net (code "37") (name "COM1_VOUT") (class "Default")
      (node (ref "C_OUT8") (pin "1") (pinfunction "1_1") (pintype "passive"))
      (node (ref "U$12") (pin "P10") (pinfunction "OUT10_P10") (pintype "bidirectional"))
      (node (ref "U$12") (pin "P11") (pinfunction "OUT11_P11") (pintype "bidirectional"))
      (node (ref "U$12") (pin "P12") (pinfunction "OUT12_P12") (pintype "bidirectional"))
      (node (ref "U$12") (pin "P13") (pinfunction "OUT13_P13") (pintype "bidirectional"))
      (node (ref "U$12") (pin "P19") (pinfunction "OUT19_P19") (pintype "bidirectional"))
      (node (ref "U$12") (pin "P20") (pinfunction "OUT20_P20") (pintype "bidirectional"))
      (node (ref "U$12") (pin "P21") (pinfunction "OUT21_P21") (pintype "bidirectional"))
      (node (ref "U$12") (pin "P22") (pinfunction "OUT22_P22") (pintype "bidirectional"))
      (node (ref "U$12") (pin "P23") (pinfunction "OUT23_P23") (pintype "bidirectional"))
      (node (ref "U$12") (pin "P24") (pinfunction "OUT24_P24") (pintype "bidirectional"))
      (node (ref "U$12") (pin "P6") (pinfunction "OUT6_P6") (pintype "bidirectional"))
      (node (ref "U$12") (pin "P7") (pinfunction "OUT7_P7") (pintype "bidirectional"))
      (node (ref "U$12") (pin "P8") (pinfunction "OUT8_P8") (pintype "bidirectional"))
      (node (ref "U$12") (pin "P9") (pinfunction "OUT9_P9") (pintype "bidirectional"))
      (node (ref "U$2") (pin "P$101") (pinfunction "COM1_VBAT_P$101") (pintype "bidirectional"))
      (node (ref "U$2") (pin "P$103") (pinfunction "COM1_VBAT_P$103") (pintype "bidirectional"))
    )
    (net (code "38") (name "COM2_EN") (class "Default")
      (node (ref "D8") (pin "A") (pinfunction "A_A") (pintype "passive"))
      (node (ref "J3") (pin "2") (pinfunction "2_2") (pintype "passive"))
      (node (ref "R7") (pin "2") (pinfunction "2_2") (pintype "passive"))
      (node (ref "U$11") (pin "P33") (pinfunction "EN_P33") (pintype "bidirectional"))
      (node (ref "U$15") (pin "P2.5_GPIO") (pinfunction "P2.5_GPIO_P2.5_GPIO") (pintype "bidirectional"))
    )
    (net (code "39") (name "COM2_IMON") (class "Default")
      (node (ref "R_AN3") (pin "2") (pinfunction "2_2") (pintype "passive"))
      (node (ref "R_IMON7") (pin "2") (pinfunction "2_2") (pintype "passive"))
      (node (ref "U$11") (pin "P2") (pinfunction "IMON_P2") (pintype "bidirectional"))
    )
    (net (code "40") (name "COM2_VOUT") (class "Default")
      (node (ref "C_OUT7") (pin "1") (pinfunction "1_1") (pintype "passive"))
      (node (ref "U$11") (pin "P10") (pinfunction "OUT10_P10") (pintype "bidirectional"))
      (node (ref "U$11") (pin "P11") (pinfunction "OUT11_P11") (pintype "bidirectional"))
      (node (ref "U$11") (pin "P12") (pinfunction "OUT12_P12") (pintype "bidirectional"))
      (node (ref "U$11") (pin "P13") (pinfunction "OUT13_P13") (pintype "bidirectional"))
      (node (ref "U$11") (pin "P19") (pinfunction "OUT19_P19") (pintype "bidirectional"))
      (node (ref "U$11") (pin "P20") (pinfunction "OUT20_P20") (pintype "bidirectional"))
      (node (ref "U$11") (pin "P21") (pinfunction "OUT21_P21") (pintype "bidirectional"))
      (node (ref "U$11") (pin "P22") (pinfunction "OUT22_P22") (pintype "bidirectional"))
      (node (ref "U$11") (pin "P23") (pinfunction "OUT23_P23") (pintype "bidirectional"))
      (node (ref "U$11") (pin "P24") (pinfunction "OUT24_P24") (pintype "bidirectional"))
      (node (ref "U$11") (pin "P6") (pinfunction "OUT6_P6") (pintype "bidirectional"))
      (node (ref "U$11") (pin "P7") (pinfunction "OUT7_P7") (pintype "bidirectional"))
      (node (ref "U$11") (pin "P8") (pinfunction "OUT8_P8") (pintype "bidirectional"))
      (node (ref "U$11") (pin "P9") (pinfunction "OUT9_P9") (pintype "bidirectional"))
      (node (ref "U$2") (pin "P$94") (pinfunction "RAHS_GND_P$94") (pintype "bidirectional"))
      (node (ref "U$2") (pin "P$97") (pinfunction "COM2_VBAT_P$97") (pintype "bidirectional"))
      (node (ref "U$2") (pin "P$99") (pinfunction "COM2_VBAT_P$99") (pintype "bidirectional"))
    )
    (net (code "41") (name "DEPLOYMENT_VOUT") (class "Default")
      (node (ref "C_OUT5") (pin "1") (pinfunction "1_1") (pintype "passive"))
      (node (ref "J1") (pin "1") (pinfunction "1_1") (pintype "passive"))
      (node (ref "U$9") (pin "P10") (pinfunction "OUT10_P10") (pintype "bidirectional"))
      (node (ref "U$9") (pin "P11") (pinfunction "OUT11_P11") (pintype "bidirectional"))
      (node (ref "U$9") (pin "P12") (pinfunction "OUT12_P12") (pintype "bidirectional"))
      (node (ref "U$9") (pin "P13") (pinfunction "OUT13_P13") (pintype "bidirectional"))
      (node (ref "U$9") (pin "P19") (pinfunction "OUT19_P19") (pintype "bidirectional"))
      (node (ref "U$9") (pin "P20") (pinfunction "OUT20_P20") (pintype "bidirectional"))
      (node (ref "U$9") (pin "P21") (pinfunction "OUT21_P21") (pintype "bidirectional"))
      (node (ref "U$9") (pin "P22") (pinfunction "OUT22_P22") (pintype "bidirectional"))
      (node (ref "U$9") (pin "P23") (pinfunction "OUT23_P23") (pintype "bidirectional"))
      (node (ref "U$9") (pin "P24") (pinfunction "OUT24_P24") (pintype "bidirectional"))
      (node (ref "U$9") (pin "P6") (pinfunction "OUT6_P6") (pintype "bidirectional"))
      (node (ref "U$9") (pin "P7") (pinfunction "OUT7_P7") (pintype "bidirectional"))
      (node (ref "U$9") (pin "P8") (pinfunction "OUT8_P8") (pintype "bidirectional"))
      (node (ref "U$9") (pin "P9") (pinfunction "OUT9_P9") (pintype "bidirectional"))
    )
    (net (code "42") (name "ESTIMAT_EN") (class "Default")
      (node (ref "D4") (pin "A") (pinfunction "A_A") (pintype "passive"))
      (node (ref "J2") (pin "4") (pinfunction "4_4") (pintype "passive"))
      (node (ref "R3") (pin "2") (pinfunction "2_2") (pintype "passive"))
      (node (ref "U$15") (pin "P4.1_GPIO") (pinfunction "P4.1_GPIO_P4.1_GPIO") (pintype "bidirectional"))
      (node (ref "U$7") (pin "P33") (pinfunction "EN_P33") (pintype "bidirectional"))
    )
    (net (code "43") (name "ESTIMAT_IMON") (class "Default")
      (node (ref "R_AN6") (pin "2") (pinfunction "2_2") (pintype "passive"))
      (node (ref "R_IMON3") (pin "2") (pinfunction "2_2") (pintype "passive"))
      (node (ref "U$7") (pin "P2") (pinfunction "IMON_P2") (pintype "bidirectional"))
    )
    (net (code "44") (name "ESTIMAT_VOUT") (class "Default")
      (node (ref "C_OUT3") (pin "1") (pinfunction "1_1") (pintype "passive"))
      (node (ref "U$2") (pin "P$77") (pinfunction "ESTIMAT_VBAT_P$77") (pintype "bidirectional"))
      (node (ref "U$2") (pin "P$79") (pinfunction "ESTIMAT_VBAT_P$79") (pintype "bidirectional"))
      (node (ref "U$7") (pin "P10") (pinfunction "OUT10_P10") (pintype "bidirectional"))
      (node (ref "U$7") (pin "P11") (pinfunction "OUT11_P11") (pintype "bidirectional"))
      (node (ref "U$7") (pin "P12") (pinfunction "OUT12_P12") (pintype "bidirectional"))
      (node (ref "U$7") (pin "P13") (pinfunction "OUT13_P13") (pintype "bidirectional"))
      (node (ref "U$7") (pin "P19") (pinfunction "OUT19_P19") (pintype "bidirectional"))
      (node (ref "U$7") (pin "P20") (pinfunction "OUT20_P20") (pintype "bidirectional"))
      (node (ref "U$7") (pin "P21") (pinfunction "OUT21_P21") (pintype "bidirectional"))
      (node (ref "U$7") (pin "P22") (pinfunction "OUT22_P22") (pintype "bidirectional"))
      (node (ref "U$7") (pin "P23") (pinfunction "OUT23_P23") (pintype "bidirectional"))
      (node (ref "U$7") (pin "P24") (pinfunction "OUT24_P24") (pintype "bidirectional"))
      (node (ref "U$7") (pin "P6") (pinfunction "OUT6_P6") (pintype "bidirectional"))
      (node (ref "U$7") (pin "P7") (pinfunction "OUT7_P7") (pintype "bidirectional"))
      (node (ref "U$7") (pin "P8") (pinfunction "OUT8_P8") (pintype "bidirectional"))
      (node (ref "U$7") (pin "P9") (pinfunction "OUT9_P9") (pintype "bidirectional"))
    )
    (net (code "45") (name "GND") (class "Default")
      (node (ref "C1") (pin "2") (pinfunction "2_2") (pintype "passive"))
      (node (ref "C2") (pin "2") (pinfunction "2_2") (pintype "passive"))
      (node (ref "C3") (pin "2") (pinfunction "2_2") (pintype "passive"))
      (node (ref "C4") (pin "2") (pinfunction "2_2") (pintype "passive"))
      (node (ref "C5") (pin "2") (pinfunction "2_2") (pintype "passive"))
      (node (ref "C6") (pin "2") (pinfunction "2_2") (pintype "passive"))
      (node (ref "C7") (pin "2") (pinfunction "2_2") (pintype "passive"))
      (node (ref "C8") (pin "2") (pinfunction "2_2") (pintype "passive"))
      (node (ref "C9") (pin "2") (pinfunction "2_2") (pintype "passive"))
      (node (ref "CA1") (pin "2") (pinfunction "2_2") (pintype "passive"))
      (node (ref "CA10") (pin "2") (pinfunction "2_2") (pintype "passive"))
      (node (ref "CA11") (pin "2") (pinfunction "2_2") (pintype "passive"))
      (node (ref "CA2") (pin "2") (pinfunction "2_2") (pintype "passive"))
      (node (ref "CA3") (pin "2") (pinfunction "2_2") (pintype "passive"))
      (node (ref "CA4") (pin "2") (pinfunction "2_2") (pintype "passive"))
      (node (ref "CA5") (pin "2") (pinfunction "2_2") (pintype "passive"))
      (node (ref "CA6") (pin "2") (pinfunction "2_2") (pintype "passive"))
      (node (ref "CA7") (pin "2") (pinfunction "2_2") (pintype "passive"))
      (node (ref "CA8") (pin "2") (pinfunction "2_2") (pintype "passive"))
      (node (ref "CA9") (pin "2") (pinfunction "2_2") (pintype "passive"))
      (node (ref "CIN2") (pin "2") (pinfunction "2_2") (pintype "passive"))
      (node (ref "CIN3") (pin "2") (pinfunction "2_2") (pintype "passive"))
      (node (ref "CIN4") (pin "2") (pinfunction "2_2") (pintype "passive"))
      (node (ref "CIN5") (pin "2") (pinfunction "2_2") (pintype "passive"))
      (node (ref "CINTV1") (pin "2") (pinfunction "2_2") (pintype "passive"))
      (node (ref "CINTV2") (pin "2") (pinfunction "2_2") (pintype "passive"))
      (node (ref "CO1") (pin "2") (pinfunction "2_2") (pintype "passive"))
      (node (ref "CO2") (pin "2") (pinfunction "2_2") (pintype "passive"))
      (node (ref "CO3") (pin "2") (pinfunction "2_2") (pintype "passive"))
      (node (ref "CO4") (pin "2") (pinfunction "2_2") (pintype "passive"))
      (node (ref "CO5") (pin "2") (pinfunction "2_2") (pintype "passive"))
      (node (ref "CO6") (pin "2") (pinfunction "2_2") (pintype "passive"))
      (node (ref "CSYNC3") (pin "2") (pinfunction "2_2") (pintype "passive"))
      (node (ref "CSYNC5") (pin "2") (pinfunction "2_2") (pintype "passive"))
      (node (ref "CV1") (pin "2") (pinfunction "2_2") (pintype "passive"))
      (node (ref "CV2") (pin "2") (pinfunction "2_2") (pintype "passive"))
      (node (ref "CV3") (pin "2") (pinfunction "2_2") (pintype "passive"))
      (node (ref "CV4") (pin "2") (pinfunction "2_2") (pintype "passive"))
      (node (ref "CV5") (pin "2") (pinfunction "2_2") (pintype "passive"))
      (node (ref "CV6") (pin "2") (pinfunction "2_2") (pintype "passive"))
      (node (ref "C_OUT") (pin "2") (pinfunction "2_2") (pintype "passive"))
      (node (ref "C_OUT1") (pin "2") (pinfunction "2_2") (pintype "passive"))
      (node (ref "C_OUT2") (pin "2") (pinfunction "2_2") (pintype "passive"))
      (node (ref "C_OUT3") (pin "2") (pinfunction "2_2") (pintype "passive"))
      (node (ref "C_OUT4") (pin "2") (pinfunction "2_2") (pintype "passive"))
      (node (ref "C_OUT5") (pin "2") (pinfunction "2_2") (pintype "passive"))
      (node (ref "C_OUT6") (pin "2") (pinfunction "2_2") (pintype "passive"))
      (node (ref "C_OUT7") (pin "2") (pinfunction "2_2") (pintype "passive"))
      (node (ref "C_OUT8") (pin "2") (pinfunction "2_2") (pintype "passive"))
      (node (ref "C_TIMER") (pin "2") (pinfunction "2_2") (pintype "passive"))
      (node (ref "C_TIMER1") (pin "2") (pinfunction "2_2") (pintype "passive"))
      (node (ref "C_TIMER2") (pin "2") (pinfunction "2_2") (pintype "passive"))
      (node (ref "C_TIMER3") (pin "2") (pinfunction "2_2") (pintype "passive"))
      (node (ref "C_TIMER4") (pin "2") (pinfunction "2_2") (pintype "passive"))
      (node (ref "C_TIMER5") (pin "2") (pinfunction "2_2") (pintype "passive"))
      (node (ref "C_TIMER6") (pin "2") (pinfunction "2_2") (pintype "passive"))
      (node (ref "C_TIMER7") (pin "2") (pinfunction "2_2") (pintype "passive"))
      (node (ref "C_TIMER8") (pin "2") (pinfunction "2_2") (pintype "passive"))
      (node (ref "IC1") (pin "2") (pinfunction "GND_2") (pintype "power_in"))
      (node (ref "IC2") (pin "2") (pinfunction "GND_2") (pintype "power_in"))
      (node (ref "J1") (pin "2") (pinfunction "2_2") (pintype "passive"))
      (node (ref "R1") (pin "1") (pinfunction "1_1") (pintype "passive"))
      (node (ref "R10") (pin "1") (pinfunction "1_1") (pintype "passive"))
      (node (ref "R13") (pin "1") (pinfunction "1_1") (pintype "passive"))
      (node (ref "R2") (pin "1") (pinfunction "1_1") (pintype "passive"))
      (node (ref "R3") (pin "1") (pinfunction "1_1") (pintype "passive"))
      (node (ref "R4") (pin "1") (pinfunction "1_1") (pintype "passive"))
      (node (ref "R5") (pin "1") (pinfunction "1_1") (pintype "passive"))
      (node (ref "R6") (pin "1") (pinfunction "1_1") (pintype "passive"))
      (node (ref "R7") (pin "1") (pinfunction "1_1") (pintype "passive"))
      (node (ref "R8") (pin "1") (pinfunction "1_1") (pintype "passive"))
      (node (ref "R9") (pin "1") (pinfunction "1_1") (pintype "passive"))
      (node (ref "RSYNC1") (pin "2") (pinfunction "2_2") (pintype "passive"))
      (node (ref "RSYNC2") (pin "2") (pinfunction "2_2") (pintype "passive"))
      (node (ref "R_3.3V") (pin "1") (pinfunction "1_1") (pintype "passive"))
      (node (ref "R_5V") (pin "1") (pinfunction "1_1") (pintype "passive"))
      (node (ref "R_ADCS2") (pin "1") (pinfunction "1_1") (pintype "passive"))
      (node (ref "R_BOOT") (pin "1") (pinfunction "1_1") (pintype "passive"))
      (node (ref "R_COM1") (pin "1") (pinfunction "1_1") (pintype "passive"))
      (node (ref "R_COM2") (pin "1") (pinfunction "1_1") (pintype "passive"))
      (node (ref "R_EST") (pin "1") (pinfunction "1_1") (pintype "passive"))
      (node (ref "R_IMON") (pin "1") (pinfunction "1_1") (pintype "passive"))
      (node (ref "R_IMON1") (pin "1") (pinfunction "1_1") (pintype "passive"))
      (node (ref "R_IMON2") (pin "1") (pinfunction "1_1") (pintype "passive"))
      (node (ref "R_IMON3") (pin "1") (pinfunction "1_1") (pintype "passive"))
      (node (ref "R_IMON4") (pin "1") (pinfunction "1_1") (pintype "passive"))
      (node (ref "R_IMON5") (pin "1") (pinfunction "1_1") (pintype "passive"))
      (node (ref "R_IMON6") (pin "1") (pinfunction "1_1") (pintype "passive"))
      (node (ref "R_IMON7") (pin "1") (pinfunction "1_1") (pintype "passive"))
      (node (ref "R_IMON8") (pin "1") (pinfunction "1_1") (pintype "passive"))
      (node (ref "R_PPT") (pin "1") (pinfunction "1_1") (pintype "passive"))
      (node (ref "R_PROG") (pin "1") (pinfunction "1_1") (pintype "passive"))
      (node (ref "R_PROG1") (pin "1") (pinfunction "1_1") (pintype "passive"))
      (node (ref "R_PROG2") (pin "1") (pinfunction "1_1") (pintype "passive"))
      (node (ref "R_PROG3") (pin "1") (pinfunction "1_1") (pintype "passive"))
      (node (ref "R_PROG4") (pin "1") (pinfunction "1_1") (pintype "passive"))
      (node (ref "R_PROG5") (pin "1") (pinfunction "1_1") (pintype "passive"))
      (node (ref "R_PROG6") (pin "1") (pinfunction "1_1") (pintype "passive"))
      (node (ref "R_PROG7") (pin "1") (pinfunction "1_1") (pintype "passive"))
      (node (ref "R_PROG8") (pin "1") (pinfunction "1_1") (pintype "passive"))
      (node (ref "R_RAHS") (pin "1") (pinfunction "1_1") (pintype "passive"))
      (node (ref "U$1") (pin "P$37") (pinfunction "GND37_P$37") (pintype "bidirectional"))
      (node (ref "U$1") (pin "P1") (pinfunction "OV_P1") (pintype "bidirectional"))
      (node (ref "U$1") (pin "P28") (pinfunction "GND28_P28") (pintype "bidirectional"))
      (node (ref "U$1") (pin "P32") (pinfunction "GND32_P32") (pintype "bidirectional"))
      (node (ref "U$1") (pin "P36") (pinfunction "GND36_P36") (pintype "bidirectional"))
      (node (ref "U$1") (pin "P4") (pinfunction "GND4_P4") (pintype "bidirectional"))
      (node (ref "U$10") (pin "P$37") (pinfunction "GND37_P$37") (pintype "bidirectional"))
      (node (ref "U$10") (pin "P1") (pinfunction "OV_P1") (pintype "bidirectional"))
      (node (ref "U$10") (pin "P28") (pinfunction "GND28_P28") (pintype "bidirectional"))
      (node (ref "U$10") (pin "P32") (pinfunction "GND32_P32") (pintype "bidirectional"))
      (node (ref "U$10") (pin "P36") (pinfunction "GND36_P36") (pintype "bidirectional"))
      (node (ref "U$10") (pin "P4") (pinfunction "GND4_P4") (pintype "bidirectional"))
      (node (ref "U$11") (pin "P$37") (pinfunction "GND37_P$37") (pintype "bidirectional"))
      (node (ref "U$11") (pin "P1") (pinfunction "OV_P1") (pintype "bidirectional"))
      (node (ref "U$11") (pin "P28") (pinfunction "GND28_P28") (pintype "bidirectional"))
      (node (ref "U$11") (pin "P32") (pinfunction "GND32_P32") (pintype "bidirectional"))
      (node (ref "U$11") (pin "P36") (pinfunction "GND36_P36") (pintype "bidirectional"))
      (node (ref "U$11") (pin "P4") (pinfunction "GND4_P4") (pintype "bidirectional"))
      (node (ref "U$12") (pin "P$37") (pinfunction "GND37_P$37") (pintype "bidirectional"))
      (node (ref "U$12") (pin "P1") (pinfunction "OV_P1") (pintype "bidirectional"))
      (node (ref "U$12") (pin "P28") (pinfunction "GND28_P28") (pintype "bidirectional"))
      (node (ref "U$12") (pin "P32") (pinfunction "GND32_P32") (pintype "bidirectional"))
      (node (ref "U$12") (pin "P36") (pinfunction "GND36_P36") (pintype "bidirectional"))
      (node (ref "U$12") (pin "P4") (pinfunction "GND4_P4") (pintype "bidirectional"))
      (node (ref "U$13") (pin "P$8") (pinfunction "GND_P$8") (pintype "bidirectional"))
      (node (ref "U$13") (pin "P$9") (pinfunction "GNDP_P$9") (pintype "bidirectional"))
      (node (ref "U$14") (pin "P$8") (pinfunction "GND_P$8") (pintype "bidirectional"))
      (node (ref "U$14") (pin "P$9") (pinfunction "GNDP_P$9") (pintype "bidirectional"))
      (node (ref "U$15") (pin "GND@1") (pinfunction "GND_GND@1") (pintype "bidirectional"))
      (node (ref "U$15") (pin "GND@10") (pinfunction "GND_GND@10") (pintype "bidirectional"))
      (node (ref "U$15") (pin "GND@11") (pinfunction "GND_GND@11") (pintype "bidirectional"))
      (node (ref "U$15") (pin "GND@12") (pinfunction "GND_GND@12") (pintype "bidirectional"))
      (node (ref "U$15") (pin "GND@13") (pinfunction "GND_GND@13") (pintype "bidirectional"))
      (node (ref "U$15") (pin "GND@14") (pinfunction "GND_GND@14") (pintype "bidirectional"))
      (node (ref "U$15") (pin "GND@15") (pinfunction "GND_GND@15") (pintype "bidirectional"))
      (node (ref "U$15") (pin "GND@16") (pinfunction "GND_GND@16") (pintype "bidirectional"))
      (node (ref "U$15") (pin "GND@17") (pinfunction "GND_GND@17") (pintype "bidirectional"))
      (node (ref "U$15") (pin "GND@2") (pinfunction "GND_GND@2") (pintype "bidirectional"))
      (node (ref "U$15") (pin "GND@26") (pinfunction "GND_GND@26") (pintype "bidirectional"))
      (node (ref "U$15") (pin "GND@3") (pinfunction "GND_GND@3") (pintype "bidirectional"))
      (node (ref "U$15") (pin "GND@4") (pinfunction "GND_GND@4") (pintype "bidirectional"))
      (node (ref "U$15") (pin "GND@5") (pinfunction "GND_GND@5") (pintype "bidirectional"))
      (node (ref "U$15") (pin "GND@7") (pinfunction "GND_GND@7") (pintype "bidirectional"))
      (node (ref "U$15") (pin "GND@8") (pinfunction "GND_GND@8") (pintype "bidirectional"))
      (node (ref "U$15") (pin "GND@9") (pinfunction "GND_GND@9") (pintype "bidirectional"))
      (node (ref "U$16") (pin "5") (pinfunction "GND_5") (pintype "bidirectional"))
      (node (ref "U$16") (pin "6") (pinfunction "GND_6") (pintype "bidirectional"))
      (node (ref "U$2") (pin "P$1") (pinfunction "PPT_GND_P$1") (pintype "bidirectional"))
      (node (ref "U$2") (pin "P$100") (pinfunction "COM2_GND_P$100") (pintype "bidirectional"))
      (node (ref "U$2") (pin "P$102") (pinfunction "COM1_GND_P$102") (pintype "bidirectional"))
      (node (ref "U$2") (pin "P$104") (pinfunction "COM1_GND_P$104") (pintype "bidirectional"))
      (node (ref "U$2") (pin "P$11") (pinfunction "PPT_GND_P$11") (pintype "bidirectional"))
      (node (ref "U$2") (pin "P$14") (pinfunction "PPT_GND_P$14") (pintype "bidirectional"))
      (node (ref "U$2") (pin "P$16") (pinfunction "PPT_GND_P$16") (pintype "bidirectional"))
      (node (ref "U$2") (pin "P$17") (pinfunction "DISTRI_GND_P$17") (pintype "bidirectional"))
      (node (ref "U$2") (pin "P$19") (pinfunction "DISTRI_GND_P$19") (pintype "bidirectional"))
      (node (ref "U$2") (pin "P$22") (pinfunction "DISTRI_GND_P$22") (pintype "bidirectional"))
      (node (ref "U$2") (pin "P$24") (pinfunction "DISTRI_GND_P$24") (pintype "bidirectional"))
      (node (ref "U$2") (pin "P$25") (pinfunction "DISTRI_GND_P$25") (pintype "bidirectional"))
      (node (ref "U$2") (pin "P$27") (pinfunction "DISTRI_GND_P$27") (pintype "bidirectional"))
      (node (ref "U$2") (pin "P$3") (pinfunction "PPT_GND_P$3") (pintype "bidirectional"))
      (node (ref "U$2") (pin "P$30") (pinfunction "DISTRI_GND_P$30") (pintype "bidirectional"))
      (node (ref "U$2") (pin "P$32") (pinfunction "DISTRI_GND_P$32") (pintype "bidirectional"))
      (node (ref "U$2") (pin "P$46") (pinfunction "MCU_GND_P$46") (pintype "bidirectional"))
      (node (ref "U$2") (pin "P$47") (pinfunction "MCU_GND_P$47") (pintype "bidirectional"))
      (node (ref "U$2") (pin "P$58") (pinfunction "MCU_GND_P$58") (pintype "bidirectional"))
      (node (ref "U$2") (pin "P$59") (pinfunction "MCU_GND_P$59") (pintype "bidirectional"))
      (node (ref "U$2") (pin "P$6") (pinfunction "PPT_GND_P$6") (pintype "bidirectional"))
      (node (ref "U$2") (pin "P$78") (pinfunction "ESTIMAT_GND_P$78") (pintype "bidirectional"))
      (node (ref "U$2") (pin "P$8") (pinfunction "PPT_GND_P$8") (pintype "bidirectional"))
      (node (ref "U$2") (pin "P$80") (pinfunction "ESTIMAT_GND_P$80") (pintype "bidirectional"))
      (node (ref "U$2") (pin "P$82") (pinfunction "ADCS2_GND_P$82") (pintype "bidirectional"))
      (node (ref "U$2") (pin "P$84") (pinfunction "ADCS2_GND_P$84") (pintype "bidirectional"))
      (node (ref "U$2") (pin "P$86") (pinfunction "BDOT_GND_P$86") (pintype "bidirectional"))
      (node (ref "U$2") (pin "P$88") (pinfunction "BDOT_GND_P$88") (pintype "bidirectional"))
      (node (ref "U$2") (pin "P$9") (pinfunction "PPT_GND_P$9") (pintype "bidirectional"))
      (node (ref "U$2") (pin "P$93") (pinfunction "RAHS_VBAT_P$93") (pintype "bidirectional"))
      (node (ref "U$2") (pin "P$98") (pinfunction "COM2_GND_P$98") (pintype "bidirectional"))
      (node (ref "U$5") (pin "P$37") (pinfunction "GND37_P$37") (pintype "bidirectional"))
      (node (ref "U$5") (pin "P1") (pinfunction "OV_P1") (pintype "bidirectional"))
      (node (ref "U$5") (pin "P28") (pinfunction "GND28_P28") (pintype "bidirectional"))
      (node (ref "U$5") (pin "P32") (pinfunction "GND32_P32") (pintype "bidirectional"))
      (node (ref "U$5") (pin "P36") (pinfunction "GND36_P36") (pintype "bidirectional"))
      (node (ref "U$5") (pin "P4") (pinfunction "GND4_P4") (pintype "bidirectional"))
      (node (ref "U$6") (pin "P$37") (pinfunction "GND37_P$37") (pintype "bidirectional"))
      (node (ref "U$6") (pin "P1") (pinfunction "OV_P1") (pintype "bidirectional"))
      (node (ref "U$6") (pin "P28") (pinfunction "GND28_P28") (pintype "bidirectional"))
      (node (ref "U$6") (pin "P32") (pinfunction "GND32_P32") (pintype "bidirectional"))
      (node (ref "U$6") (pin "P36") (pinfunction "GND36_P36") (pintype "bidirectional"))
      (node (ref "U$6") (pin "P4") (pinfunction "GND4_P4") (pintype "bidirectional"))
      (node (ref "U$7") (pin "P$37") (pinfunction "GND37_P$37") (pintype "bidirectional"))
      (node (ref "U$7") (pin "P1") (pinfunction "OV_P1") (pintype "bidirectional"))
      (node (ref "U$7") (pin "P28") (pinfunction "GND28_P28") (pintype "bidirectional"))
      (node (ref "U$7") (pin "P32") (pinfunction "GND32_P32") (pintype "bidirectional"))
      (node (ref "U$7") (pin "P36") (pinfunction "GND36_P36") (pintype "bidirectional"))
      (node (ref "U$7") (pin "P4") (pinfunction "GND4_P4") (pintype "bidirectional"))
      (node (ref "U$8") (pin "P$37") (pinfunction "GND37_P$37") (pintype "bidirectional"))
      (node (ref "U$8") (pin "P1") (pinfunction "OV_P1") (pintype "bidirectional"))
      (node (ref "U$8") (pin "P28") (pinfunction "GND28_P28") (pintype "bidirectional"))
      (node (ref "U$8") (pin "P32") (pinfunction "GND32_P32") (pintype "bidirectional"))
      (node (ref "U$8") (pin "P36") (pinfunction "GND36_P36") (pintype "bidirectional"))
      (node (ref "U$8") (pin "P4") (pinfunction "GND4_P4") (pintype "bidirectional"))
      (node (ref "U$9") (pin "P$37") (pinfunction "GND37_P$37") (pintype "bidirectional"))
      (node (ref "U$9") (pin "P1") (pinfunction "OV_P1") (pintype "bidirectional"))
      (node (ref "U$9") (pin "P28") (pinfunction "GND28_P28") (pintype "bidirectional"))
      (node (ref "U$9") (pin "P32") (pinfunction "GND32_P32") (pintype "bidirectional"))
      (node (ref "U$9") (pin "P36") (pinfunction "GND36_P36") (pintype "bidirectional"))
      (node (ref "U$9") (pin "P4") (pinfunction "GND4_P4") (pintype "bidirectional"))
    )
    (net (code "46") (name "MAG_VOUT") (class "Default")
      (node (ref "C_OUT4") (pin "1") (pinfunction "1_1") (pintype "passive"))
      (node (ref "U$2") (pin "P$85") (pinfunction "BDOT_VBAT_P$85") (pintype "bidirectional"))
      (node (ref "U$2") (pin "P$87") (pinfunction "BDOT_VBAT_P$87") (pintype "bidirectional"))
      (node (ref "U$8") (pin "P10") (pinfunction "OUT10_P10") (pintype "bidirectional"))
      (node (ref "U$8") (pin "P11") (pinfunction "OUT11_P11") (pintype "bidirectional"))
      (node (ref "U$8") (pin "P12") (pinfunction "OUT12_P12") (pintype "bidirectional"))
      (node (ref "U$8") (pin "P13") (pinfunction "OUT13_P13") (pintype "bidirectional"))
      (node (ref "U$8") (pin "P19") (pinfunction "OUT19_P19") (pintype "bidirectional"))
      (node (ref "U$8") (pin "P20") (pinfunction "OUT20_P20") (pintype "bidirectional"))
      (node (ref "U$8") (pin "P21") (pinfunction "OUT21_P21") (pintype "bidirectional"))
      (node (ref "U$8") (pin "P22") (pinfunction "OUT22_P22") (pintype "bidirectional"))
      (node (ref "U$8") (pin "P23") (pinfunction "OUT23_P23") (pintype "bidirectional"))
      (node (ref "U$8") (pin "P24") (pinfunction "OUT24_P24") (pintype "bidirectional"))
      (node (ref "U$8") (pin "P6") (pinfunction "OUT6_P6") (pintype "bidirectional"))
      (node (ref "U$8") (pin "P7") (pinfunction "OUT7_P7") (pintype "bidirectional"))
      (node (ref "U$8") (pin "P8") (pinfunction "OUT8_P8") (pintype "bidirectional"))
      (node (ref "U$8") (pin "P9") (pinfunction "OUT9_P9") (pintype "bidirectional"))
    )
    (net (code "47") (name "Net-(D1-PadC)") (class "Default")
      (node (ref "D1") (pin "C") (pinfunction "C_C") (pintype "passive"))
      (node (ref "R_PPT") (pin "2") (pinfunction "2_2") (pintype "passive"))
    )
    (net (code "48") (name "Net-(D2-PadC)") (class "Default")
      (node (ref "D2") (pin "C") (pinfunction "C_C") (pintype "passive"))
      (node (ref "R_5V") (pin "2") (pinfunction "2_2") (pintype "passive"))
    )
    (net (code "49") (name "Net-(D3-PadC)") (class "Default")
      (node (ref "D3") (pin "C") (pinfunction "C_C") (pintype "passive"))
      (node (ref "R_3.3V") (pin "2") (pinfunction "2_2") (pintype "passive"))
    )
    (net (code "50") (name "Net-(D4-PadC)") (class "Default")
      (node (ref "D4") (pin "C") (pinfunction "C_C") (pintype "passive"))
      (node (ref "R_EST") (pin "2") (pinfunction "2_2") (pintype "passive"))
    )
    (net (code "51") (name "Net-(D5-PadC)") (class "Default")
      (node (ref "D5") (pin "C") (pinfunction "C_C") (pintype "passive"))
      (node (ref "R_ADCS2") (pin "2") (pinfunction "2_2") (pintype "passive"))
    )
    (net (code "52") (name "Net-(D6-PadC)") (class "Default")
      (node (ref "D6") (pin "C") (pinfunction "C_C") (pintype "passive"))
      (node (ref "R_BOOT") (pin "2") (pinfunction "2_2") (pintype "passive"))
    )
    (net (code "53") (name "Net-(D7-PadC)") (class "Default")
      (node (ref "D7") (pin "C") (pinfunction "C_C") (pintype "passive"))
      (node (ref "R_RAHS") (pin "2") (pinfunction "2_2") (pintype "passive"))
    )
    (net (code "54") (name "Net-(D8-PadC)") (class "Default")
      (node (ref "D8") (pin "C") (pinfunction "C_C") (pintype "passive"))
      (node (ref "R_COM2") (pin "2") (pinfunction "2_2") (pintype "passive"))
    )
    (net (code "55") (name "Net-(D9-PadC)") (class "Default")
      (node (ref "D9") (pin "C") (pinfunction "C_C") (pintype "passive"))
      (node (ref "R_COM1") (pin "2") (pinfunction "2_2") (pintype "passive"))
    )
    (net (code "56") (name "Net-(L1-P$2)") (class "Default")
      (node (ref "L1") (pin "2") (pinfunction "P$2_2") (pintype "bidirectional"))
      (node (ref "U$13") (pin "P$1") (pinfunction "SW_P$1") (pintype "bidirectional"))
    )
    (net (code "57") (name "Net-(L2-P$2)") (class "Default")
      (node (ref "L2") (pin "2") (pinfunction "P$2_2") (pintype "bidirectional"))
      (node (ref "U$14") (pin "P$1") (pinfunction "SW_P$1") (pintype "bidirectional"))
    )
    (net (code "58") (name "Net-(U$1-DRAIN14)") (class "Default")
      (node (ref "R_SENSE") (pin "2") (pinfunction "2_2") (pintype "passive"))
      (node (ref "U$1") (pin "P$38") (pinfunction "DRAIN38_P$38") (pintype "bidirectional"))
      (node (ref "U$1") (pin "P14") (pinfunction "DRAIN14_P14") (pintype "bidirectional"))
      (node (ref "U$1") (pin "P15") (pinfunction "DRAIN15_P15") (pintype "bidirectional"))
      (node (ref "U$1") (pin "P16") (pinfunction "DRAIN16_P16") (pintype "bidirectional"))
      (node (ref "U$1") (pin "P17") (pinfunction "DRAIN17_P17") (pintype "bidirectional"))
      (node (ref "U$1") (pin "P18") (pinfunction "DRAIN18_P18") (pintype "bidirectional"))
      (node (ref "U$1") (pin "P26") (pinfunction "SENSE_P26") (pintype "bidirectional"))
      (node (ref "U$1") (pin "P27") (pinfunction "DRAIN27_P27") (pintype "bidirectional"))
      (node (ref "U$1") (pin "P5") (pinfunction "DRAIN5_P5") (pintype "bidirectional"))
    )
    (net (code "59") (name "Net-(U$1-PROG)") (class "Default")
      (node (ref "R_PROG") (pin "2") (pinfunction "2_2") (pintype "passive"))
      (node (ref "U$1") (pin "P34") (pinfunction "PROG_P34") (pintype "bidirectional"))
    )
    (net (code "60") (name "Net-(U$1-SET)") (class "Default")
      (node (ref "R_SET") (pin "1") (pinfunction "1_1") (pintype "passive"))
      (node (ref "U$1") (pin "P3") (pinfunction "SET_P3") (pintype "bidirectional"))
    )
    (net (code "61") (name "Net-(U$1-TIMER)") (class "Default")
      (node (ref "C_TIMER") (pin "1") (pinfunction "1_1") (pintype "passive"))
      (node (ref "U$1") (pin "P35") (pinfunction "TIMER_P35") (pintype "bidirectional"))
    )
    (net (code "62") (name "Net-(U$5-DRAIN14)") (class "Default")
      (node (ref "R_SENSE1") (pin "2") (pinfunction "2_2") (pintype "passive"))
      (node (ref "U$5") (pin "P$38") (pinfunction "DRAIN38_P$38") (pintype "bidirectional"))
      (node (ref "U$5") (pin "P14") (pinfunction "DRAIN14_P14") (pintype "bidirectional"))
      (node (ref "U$5") (pin "P15") (pinfunction "DRAIN15_P15") (pintype "bidirectional"))
      (node (ref "U$5") (pin "P16") (pinfunction "DRAIN16_P16") (pintype "bidirectional"))
      (node (ref "U$5") (pin "P17") (pinfunction "DRAIN17_P17") (pintype "bidirectional"))
      (node (ref "U$5") (pin "P18") (pinfunction "DRAIN18_P18") (pintype "bidirectional"))
      (node (ref "U$5") (pin "P26") (pinfunction "SENSE_P26") (pintype "bidirectional"))
      (node (ref "U$5") (pin "P27") (pinfunction "DRAIN27_P27") (pintype "bidirectional"))
      (node (ref "U$5") (pin "P5") (pinfunction "DRAIN5_P5") (pintype "bidirectional"))
    )
    (net (code "63") (name "Net-(U$5-PROG)") (class "Default")
      (node (ref "R_PROG1") (pin "2") (pinfunction "2_2") (pintype "passive"))
      (node (ref "U$5") (pin "P34") (pinfunction "PROG_P34") (pintype "bidirectional"))
    )
    (net (code "64") (name "Net-(U$5-SET)") (class "Default")
      (node (ref "R_SET1") (pin "1") (pinfunction "1_1") (pintype "passive"))
      (node (ref "U$5") (pin "P3") (pinfunction "SET_P3") (pintype "bidirectional"))
    )
    (net (code "65") (name "Net-(U$5-TIMER)") (class "Default")
      (node (ref "C_TIMER1") (pin "1") (pinfunction "1_1") (pintype "passive"))
      (node (ref "U$5") (pin "P35") (pinfunction "TIMER_P35") (pintype "bidirectional"))
    )
    (net (code "66") (name "Net-(U$6-DRAIN14)") (class "Default")
      (node (ref "R_SENSE2") (pin "2") (pinfunction "2_2") (pintype "passive"))
      (node (ref "U$6") (pin "P$38") (pinfunction "DRAIN38_P$38") (pintype "bidirectional"))
      (node (ref "U$6") (pin "P14") (pinfunction "DRAIN14_P14") (pintype "bidirectional"))
      (node (ref "U$6") (pin "P15") (pinfunction "DRAIN15_P15") (pintype "bidirectional"))
      (node (ref "U$6") (pin "P16") (pinfunction "DRAIN16_P16") (pintype "bidirectional"))
      (node (ref "U$6") (pin "P17") (pinfunction "DRAIN17_P17") (pintype "bidirectional"))
      (node (ref "U$6") (pin "P18") (pinfunction "DRAIN18_P18") (pintype "bidirectional"))
      (node (ref "U$6") (pin "P26") (pinfunction "SENSE_P26") (pintype "bidirectional"))
      (node (ref "U$6") (pin "P27") (pinfunction "DRAIN27_P27") (pintype "bidirectional"))
      (node (ref "U$6") (pin "P5") (pinfunction "DRAIN5_P5") (pintype "bidirectional"))
    )
    (net (code "67") (name "Net-(U$6-PROG)") (class "Default")
      (node (ref "R_PROG2") (pin "2") (pinfunction "2_2") (pintype "passive"))
      (node (ref "U$6") (pin "P34") (pinfunction "PROG_P34") (pintype "bidirectional"))
    )
    (net (code "68") (name "Net-(U$6-SET)") (class "Default")
      (node (ref "R_SET2") (pin "1") (pinfunction "1_1") (pintype "passive"))
      (node (ref "U$6") (pin "P3") (pinfunction "SET_P3") (pintype "bidirectional"))
    )
    (net (code "69") (name "Net-(U$6-TIMER)") (class "Default")
      (node (ref "C_TIMER2") (pin "1") (pinfunction "1_1") (pintype "passive"))
      (node (ref "U$6") (pin "P35") (pinfunction "TIMER_P35") (pintype "bidirectional"))
    )
    (net (code "70") (name "Net-(U$7-DRAIN14)") (class "Default")
      (node (ref "R_SENSE3") (pin "2") (pinfunction "2_2") (pintype "passive"))
      (node (ref "U$7") (pin "P$38") (pinfunction "DRAIN38_P$38") (pintype "bidirectional"))
      (node (ref "U$7") (pin "P14") (pinfunction "DRAIN14_P14") (pintype "bidirectional"))
      (node (ref "U$7") (pin "P15") (pinfunction "DRAIN15_P15") (pintype "bidirectional"))
      (node (ref "U$7") (pin "P16") (pinfunction "DRAIN16_P16") (pintype "bidirectional"))
      (node (ref "U$7") (pin "P17") (pinfunction "DRAIN17_P17") (pintype "bidirectional"))
      (node (ref "U$7") (pin "P18") (pinfunction "DRAIN18_P18") (pintype "bidirectional"))
      (node (ref "U$7") (pin "P26") (pinfunction "SENSE_P26") (pintype "bidirectional"))
      (node (ref "U$7") (pin "P27") (pinfunction "DRAIN27_P27") (pintype "bidirectional"))
      (node (ref "U$7") (pin "P5") (pinfunction "DRAIN5_P5") (pintype "bidirectional"))
    )
    (net (code "71") (name "Net-(U$7-PROG)") (class "Default")
      (node (ref "R_PROG3") (pin "2") (pinfunction "2_2") (pintype "passive"))
      (node (ref "U$7") (pin "P34") (pinfunction "PROG_P34") (pintype "bidirectional"))
    )
    (net (code "72") (name "Net-(U$7-SET)") (class "Default")
      (node (ref "R_SET3") (pin "1") (pinfunction "1_1") (pintype "passive"))
      (node (ref "U$7") (pin "P3") (pinfunction "SET_P3") (pintype "bidirectional"))
    )
    (net (code "73") (name "Net-(U$7-TIMER)") (class "Default")
      (node (ref "C_TIMER3") (pin "1") (pinfunction "1_1") (pintype "passive"))
      (node (ref "U$7") (pin "P35") (pinfunction "TIMER_P35") (pintype "bidirectional"))
    )
    (net (code "74") (name "Net-(U$8-DRAIN14)") (class "Default")
      (node (ref "R_SENSE4") (pin "2") (pinfunction "2_2") (pintype "passive"))
      (node (ref "U$8") (pin "P$38") (pinfunction "DRAIN38_P$38") (pintype "bidirectional"))
      (node (ref "U$8") (pin "P14") (pinfunction "DRAIN14_P14") (pintype "bidirectional"))
      (node (ref "U$8") (pin "P15") (pinfunction "DRAIN15_P15") (pintype "bidirectional"))
      (node (ref "U$8") (pin "P16") (pinfunction "DRAIN16_P16") (pintype "bidirectional"))
      (node (ref "U$8") (pin "P17") (pinfunction "DRAIN17_P17") (pintype "bidirectional"))
      (node (ref "U$8") (pin "P18") (pinfunction "DRAIN18_P18") (pintype "bidirectional"))
      (node (ref "U$8") (pin "P26") (pinfunction "SENSE_P26") (pintype "bidirectional"))
      (node (ref "U$8") (pin "P27") (pinfunction "DRAIN27_P27") (pintype "bidirectional"))
      (node (ref "U$8") (pin "P5") (pinfunction "DRAIN5_P5") (pintype "bidirectional"))
    )
    (net (code "75") (name "Net-(U$8-PROG)") (class "Default")
      (node (ref "R_PROG4") (pin "2") (pinfunction "2_2") (pintype "passive"))
      (node (ref "U$8") (pin "P34") (pinfunction "PROG_P34") (pintype "bidirectional"))
    )
    (net (code "76") (name "Net-(U$8-SET)") (class "Default")
      (node (ref "R_SET4") (pin "1") (pinfunction "1_1") (pintype "passive"))
      (node (ref "U$8") (pin "P3") (pinfunction "SET_P3") (pintype "bidirectional"))
    )
    (net (code "77") (name "Net-(U$8-TIMER)") (class "Default")
      (node (ref "C_TIMER4") (pin "1") (pinfunction "1_1") (pintype "passive"))
      (node (ref "U$8") (pin "P35") (pinfunction "TIMER_P35") (pintype "bidirectional"))
    )
    (net (code "78") (name "Net-(U$9-DRAIN14)") (class "Default")
      (node (ref "R_SENSE5") (pin "2") (pinfunction "2_2") (pintype "passive"))
      (node (ref "U$9") (pin "P$38") (pinfunction "DRAIN38_P$38") (pintype "bidirectional"))
      (node (ref "U$9") (pin "P14") (pinfunction "DRAIN14_P14") (pintype "bidirectional"))
      (node (ref "U$9") (pin "P15") (pinfunction "DRAIN15_P15") (pintype "bidirectional"))
      (node (ref "U$9") (pin "P16") (pinfunction "DRAIN16_P16") (pintype "bidirectional"))
      (node (ref "U$9") (pin "P17") (pinfunction "DRAIN17_P17") (pintype "bidirectional"))
      (node (ref "U$9") (pin "P18") (pinfunction "DRAIN18_P18") (pintype "bidirectional"))
      (node (ref "U$9") (pin "P26") (pinfunction "SENSE_P26") (pintype "bidirectional"))
      (node (ref "U$9") (pin "P27") (pinfunction "DRAIN27_P27") (pintype "bidirectional"))
      (node (ref "U$9") (pin "P5") (pinfunction "DRAIN5_P5") (pintype "bidirectional"))
    )
    (net (code "79") (name "Net-(U$9-PROG)") (class "Default")
      (node (ref "R_PROG5") (pin "2") (pinfunction "2_2") (pintype "passive"))
      (node (ref "U$9") (pin "P34") (pinfunction "PROG_P34") (pintype "bidirectional"))
    )
    (net (code "80") (name "Net-(U$9-SET)") (class "Default")
      (node (ref "R_SET5") (pin "1") (pinfunction "1_1") (pintype "passive"))
      (node (ref "U$9") (pin "P3") (pinfunction "SET_P3") (pintype "bidirectional"))
    )
    (net (code "81") (name "Net-(U$9-TIMER)") (class "Default")
      (node (ref "C_TIMER5") (pin "1") (pinfunction "1_1") (pintype "passive"))
      (node (ref "U$9") (pin "P35") (pinfunction "TIMER_P35") (pintype "bidirectional"))
    )
    (net (code "82") (name "Net-(U$10-DRAIN14)") (class "Default")
      (node (ref "R_SENSE6") (pin "2") (pinfunction "2_2") (pintype "passive"))
      (node (ref "U$10") (pin "P$38") (pinfunction "DRAIN38_P$38") (pintype "bidirectional"))
      (node (ref "U$10") (pin "P14") (pinfunction "DRAIN14_P14") (pintype "bidirectional"))
      (node (ref "U$10") (pin "P15") (pinfunction "DRAIN15_P15") (pintype "bidirectional"))
      (node (ref "U$10") (pin "P16") (pinfunction "DRAIN16_P16") (pintype "bidirectional"))
      (node (ref "U$10") (pin "P17") (pinfunction "DRAIN17_P17") (pintype "bidirectional"))
      (node (ref "U$10") (pin "P18") (pinfunction "DRAIN18_P18") (pintype "bidirectional"))
      (node (ref "U$10") (pin "P26") (pinfunction "SENSE_P26") (pintype "bidirectional"))
      (node (ref "U$10") (pin "P27") (pinfunction "DRAIN27_P27") (pintype "bidirectional"))
      (node (ref "U$10") (pin "P5") (pinfunction "DRAIN5_P5") (pintype "bidirectional"))
    )
    (net (code "83") (name "Net-(U$10-PROG)") (class "Default")
      (node (ref "R_PROG6") (pin "2") (pinfunction "2_2") (pintype "passive"))
      (node (ref "U$10") (pin "P34") (pinfunction "PROG_P34") (pintype "bidirectional"))
    )
    (net (code "84") (name "Net-(U$10-SET)") (class "Default")
      (node (ref "R_SET6") (pin "1") (pinfunction "1_1") (pintype "passive"))
      (node (ref "U$10") (pin "P3") (pinfunction "SET_P3") (pintype "bidirectional"))
    )
    (net (code "85") (name "Net-(U$10-TIMER)") (class "Default")
      (node (ref "C_TIMER6") (pin "1") (pinfunction "1_1") (pintype "passive"))
      (node (ref "U$10") (pin "P35") (pinfunction "TIMER_P35") (pintype "bidirectional"))
    )
    (net (code "86") (name "Net-(U$11-DRAIN14)") (class "Default")
      (node (ref "R_SENSE7") (pin "2") (pinfunction "2_2") (pintype "passive"))
      (node (ref "U$11") (pin "P$38") (pinfunction "DRAIN38_P$38") (pintype "bidirectional"))
      (node (ref "U$11") (pin "P14") (pinfunction "DRAIN14_P14") (pintype "bidirectional"))
      (node (ref "U$11") (pin "P15") (pinfunction "DRAIN15_P15") (pintype "bidirectional"))
      (node (ref "U$11") (pin "P16") (pinfunction "DRAIN16_P16") (pintype "bidirectional"))
      (node (ref "U$11") (pin "P17") (pinfunction "DRAIN17_P17") (pintype "bidirectional"))
      (node (ref "U$11") (pin "P18") (pinfunction "DRAIN18_P18") (pintype "bidirectional"))
      (node (ref "U$11") (pin "P26") (pinfunction "SENSE_P26") (pintype "bidirectional"))
      (node (ref "U$11") (pin "P27") (pinfunction "DRAIN27_P27") (pintype "bidirectional"))
      (node (ref "U$11") (pin "P5") (pinfunction "DRAIN5_P5") (pintype "bidirectional"))
    )
    (net (code "87") (name "Net-(U$11-PROG)") (class "Default")
      (node (ref "R_PROG7") (pin "2") (pinfunction "2_2") (pintype "passive"))
      (node (ref "U$11") (pin "P34") (pinfunction "PROG_P34") (pintype "bidirectional"))
    )
    (net (code "88") (name "Net-(U$11-SET)") (class "Default")
      (node (ref "R_SET7") (pin "1") (pinfunction "1_1") (pintype "passive"))
      (node (ref "U$11") (pin "P3") (pinfunction "SET_P3") (pintype "bidirectional"))
    )
    (net (code "89") (name "Net-(U$11-TIMER)") (class "Default")
      (node (ref "C_TIMER7") (pin "1") (pinfunction "1_1") (pintype "passive"))
      (node (ref "U$11") (pin "P35") (pinfunction "TIMER_P35") (pintype "bidirectional"))
    )
    (net (code "90") (name "Net-(U$12-DRAIN14)") (class "Default")
      (node (ref "R_SENSE8") (pin "2") (pinfunction "2_2") (pintype "passive"))
      (node (ref "U$12") (pin "P$38") (pinfunction "DRAIN38_P$38") (pintype "bidirectional"))
      (node (ref "U$12") (pin "P14") (pinfunction "DRAIN14_P14") (pintype "bidirectional"))
      (node (ref "U$12") (pin "P15") (pinfunction "DRAIN15_P15") (pintype "bidirectional"))
      (node (ref "U$12") (pin "P16") (pinfunction "DRAIN16_P16") (pintype "bidirectional"))
      (node (ref "U$12") (pin "P17") (pinfunction "DRAIN17_P17") (pintype "bidirectional"))
      (node (ref "U$12") (pin "P18") (pinfunction "DRAIN18_P18") (pintype "bidirectional"))
      (node (ref "U$12") (pin "P26") (pinfunction "SENSE_P26") (pintype "bidirectional"))
      (node (ref "U$12") (pin "P27") (pinfunction "DRAIN27_P27") (pintype "bidirectional"))
      (node (ref "U$12") (pin "P5") (pinfunction "DRAIN5_P5") (pintype "bidirectional"))
    )
    (net (code "91") (name "Net-(U$12-PROG)") (class "Default")
      (node (ref "R_PROG8") (pin "2") (pinfunction "2_2") (pintype "passive"))
      (node (ref "U$12") (pin "P34") (pinfunction "PROG_P34") (pintype "bidirectional"))
    )
    (net (code "92") (name "Net-(U$12-SET)") (class "Default")
      (node (ref "R_SET8") (pin "1") (pinfunction "1_1") (pintype "passive"))
      (node (ref "U$12") (pin "P3") (pinfunction "SET_P3") (pintype "bidirectional"))
    )
    (net (code "93") (name "Net-(U$12-TIMER)") (class "Default")
      (node (ref "C_TIMER8") (pin "1") (pinfunction "1_1") (pintype "passive"))
      (node (ref "U$12") (pin "P35") (pinfunction "TIMER_P35") (pintype "bidirectional"))
    )
    (net (code "94") (name "Net-(U$13-FB)") (class "Default")
      (node (ref "C20") (pin "2") (pinfunction "2_2") (pintype "passive"))
      (node (ref "CSYNC2") (pin "2") (pinfunction "2_2") (pintype "passive"))
      (node (ref "CSYNC3") (pin "1") (pinfunction "1_1") (pintype "passive"))
      (node (ref "JP1") (pin "2") (pinfunction "2_2") (pintype "passive"))
      (node (ref "U$13") (pin "P$5") (pinfunction "FB_P$5") (pintype "bidirectional"))
    )
    (net (code "95") (name "Net-(U$14-FB)") (class "Default")
      (node (ref "C21") (pin "2") (pinfunction "2_2") (pintype "passive"))
      (node (ref "CSYNC4") (pin "2") (pinfunction "2_2") (pintype "passive"))
      (node (ref "CSYNC5") (pin "1") (pinfunction "1_1") (pintype "passive"))
      (node (ref "JP2") (pin "2") (pinfunction "2_2") (pintype "passive"))
      (node (ref "U$14") (pin "P$5") (pinfunction "FB_P$5") (pintype "bidirectional"))
    )
    (net (code "96") (name "Net-(U$14-INTV)") (class "Default")
      (node (ref "CINTV2") (pin "1") (pinfunction "1_1") (pintype "passive"))
      (node (ref "U$14") (pin "P$6") (pinfunction "INTV_P$6") (pintype "bidirectional"))
    )
    (net (code "97") (name "Net-(U$14-MODE)") (class "Default")
      (node (ref "RSYNC2") (pin "1") (pinfunction "1_1") (pintype "passive"))
      (node (ref "U$14") (pin "P$7") (pinfunction "MODE_P$7") (pintype "bidirectional"))
    )
    (net (code "98") (name "Net-(U$15-PadSBWTCK)") (class "Default")
      (node (ref "U$15") (pin "SBWTCK") (pinfunction "SBWTCK_SBWTCK") (pintype "bidirectional"))
      (node (ref "U$16") (pin "SBWTCK") (pinfunction "SBWTCK_SBWTCK") (pintype "bidirectional"))
    )
    (net (code "99") (name "Net-(U$16-P2.0_TXD)") (class "Default")
      (node (ref "U$15") (pin "P2.0_TXD") (pinfunction "P2.0_TXD_P2.0_TXD") (pintype "bidirectional"))
      (node (ref "U$16") (pin "3") (pinfunction "P2.0_TXD_3") (pintype "bidirectional"))
    )
    (net (code "100") (name "Net-(U$16-P2.1_RXD)") (class "Default")
      (node (ref "U$15") (pin "P2.1_RXD") (pinfunction "P2.1_RXD_P2.1_RXD") (pintype "bidirectional"))
      (node (ref "U$16") (pin "4") (pinfunction "P2.1_RXD_4") (pintype "bidirectional"))
    )
    (net (code "101") (name "Net-(U$16-P3.4_GPIO_DEBUG)") (class "Default")
      (node (ref "U$15") (pin "P3.4_GPIO_DEBUG") (pinfunction "P3.4_GPIO_DEBUG_P3.4_GPIO_DEBUG") (pintype "bidirectional"))
      (node (ref "U$16") (pin "7") (pinfunction "P3.4_GPIO_DEBUG_7") (pintype "bidirectional"))
    )
    (net (code "102") (name "Net-(U$16-P3.5_GPIO_DEBUG)") (class "Default")
      (node (ref "U$15") (pin "P3.5_GPIO_DEBUG") (pinfunction "P3.5_GPIO_DEBUG_P3.5_GPIO_DEBUG") (pintype "bidirectional"))
      (node (ref "U$16") (pin "8") (pinfunction "P3.5_GPIO_DEBUG_8") (pintype "bidirectional"))
    )
    (net (code "103") (name "Net-(U$16-SBWTDIO)") (class "Default")
      (node (ref "U$15") (pin "SBWTDIO") (pinfunction "SBWTDIO_SBWTDIO") (pintype "bidirectional"))
      (node (ref "U$16") (pin "2") (pinfunction "SBWTDIO_2") (pintype "bidirectional"))
    )
    (net (code "104") (name "PPT_EN") (class "Default")
      (node (ref "D1") (pin "A") (pinfunction "A_A") (pintype "passive"))
      (node (ref "J2") (pin "1") (pinfunction "1_1") (pintype "passive"))
      (node (ref "R10") (pin "2") (pinfunction "2_2") (pintype "passive"))
      (node (ref "U$1") (pin "P33") (pinfunction "EN_P33") (pintype "bidirectional"))
      (node (ref "U$15") (pin "P7.3_GPIO") (pinfunction "P7.3_GPIO_P7.3_GPIO") (pintype "bidirectional"))
    )
    (net (code "105") (name "PPT_IMON") (class "Default")
      (node (ref "R_AN9") (pin "2") (pinfunction "2_2") (pintype "passive"))
      (node (ref "R_IMON") (pin "2") (pinfunction "2_2") (pintype "passive"))
      (node (ref "U$1") (pin "P2") (pinfunction "IMON_P2") (pintype "bidirectional"))
    )
    (net (code "106") (name "PPT_VOUT") (class "Default")
      (node (ref "C_OUT") (pin "1") (pinfunction "1_1") (pintype "passive"))
      (node (ref "U$1") (pin "P10") (pinfunction "OUT10_P10") (pintype "bidirectional"))
      (node (ref "U$1") (pin "P11") (pinfunction "OUT11_P11") (pintype "bidirectional"))
      (node (ref "U$1") (pin "P12") (pinfunction "OUT12_P12") (pintype "bidirectional"))
      (node (ref "U$1") (pin "P13") (pinfunction "OUT13_P13") (pintype "bidirectional"))
      (node (ref "U$1") (pin "P19") (pinfunction "OUT19_P19") (pintype "bidirectional"))
      (node (ref "U$1") (pin "P20") (pinfunction "OUT20_P20") (pintype "bidirectional"))
      (node (ref "U$1") (pin "P21") (pinfunction "OUT21_P21") (pintype "bidirectional"))
      (node (ref "U$1") (pin "P22") (pinfunction "OUT22_P22") (pintype "bidirectional"))
      (node (ref "U$1") (pin "P23") (pinfunction "OUT23_P23") (pintype "bidirectional"))
      (node (ref "U$1") (pin "P24") (pinfunction "OUT24_P24") (pintype "bidirectional"))
      (node (ref "U$1") (pin "P6") (pinfunction "OUT6_P6") (pintype "bidirectional"))
      (node (ref "U$1") (pin "P7") (pinfunction "OUT7_P7") (pintype "bidirectional"))
      (node (ref "U$1") (pin "P8") (pinfunction "OUT8_P8") (pintype "bidirectional"))
      (node (ref "U$1") (pin "P9") (pinfunction "OUT9_P9") (pintype "bidirectional"))
      (node (ref "U$2") (pin "P$10") (pinfunction "PPT_VBAT_P$10") (pintype "bidirectional"))
      (node (ref "U$2") (pin "P$12") (pinfunction "PPT_VBAT_P$12") (pintype "bidirectional"))
      (node (ref "U$2") (pin "P$13") (pinfunction "PPT_VBAT_P$13") (pintype "bidirectional"))
      (node (ref "U$2") (pin "P$15") (pinfunction "PPT_VBAT_P$15") (pintype "bidirectional"))
      (node (ref "U$2") (pin "P$2") (pinfunction "PPT_VBAT_P$2") (pintype "bidirectional"))
      (node (ref "U$2") (pin "P$4") (pinfunction "PPT_VBAT_P$4") (pintype "bidirectional"))
      (node (ref "U$2") (pin "P$5") (pinfunction "PPT_VBAT_P$5") (pintype "bidirectional"))
      (node (ref "U$2") (pin "P$7") (pinfunction "PPT_VBAT_P$7") (pintype "bidirectional"))
    )
    (net (code "107") (name "RAHS_EN") (class "Default")
      (node (ref "D7") (pin "A") (pinfunction "A_A") (pintype "passive"))
      (node (ref "J2") (pin "5") (pinfunction "5_5") (pintype "passive"))
      (node (ref "R6") (pin "2") (pinfunction "2_2") (pintype "passive"))
      (node (ref "U$10") (pin "P33") (pinfunction "EN_P33") (pintype "bidirectional"))
      (node (ref "U$15") (pin "P4.2_GPIO") (pinfunction "P4.2_GPIO_P4.2_GPIO") (pintype "bidirectional"))
    )
    (net (code "108") (name "RAHS_IMON") (class "Default")
      (node (ref "R_AN5") (pin "2") (pinfunction "2_2") (pintype "passive"))
      (node (ref "R_IMON6") (pin "2") (pinfunction "2_2") (pintype "passive"))
      (node (ref "U$10") (pin "P2") (pinfunction "IMON_P2") (pintype "bidirectional"))
    )
    (net (code "109") (name "REACTION_VOUT") (class "Default")
      (node (ref "C_OUT6") (pin "1") (pinfunction "1_1") (pintype "passive"))
      (node (ref "U$10") (pin "P10") (pinfunction "OUT10_P10") (pintype "bidirectional"))
      (node (ref "U$10") (pin "P11") (pinfunction "OUT11_P11") (pintype "bidirectional"))
      (node (ref "U$10") (pin "P12") (pinfunction "OUT12_P12") (pintype "bidirectional"))
      (node (ref "U$10") (pin "P13") (pinfunction "OUT13_P13") (pintype "bidirectional"))
      (node (ref "U$10") (pin "P19") (pinfunction "OUT19_P19") (pintype "bidirectional"))
      (node (ref "U$10") (pin "P20") (pinfunction "OUT20_P20") (pintype "bidirectional"))
      (node (ref "U$10") (pin "P21") (pinfunction "OUT21_P21") (pintype "bidirectional"))
      (node (ref "U$10") (pin "P22") (pinfunction "OUT22_P22") (pintype "bidirectional"))
      (node (ref "U$10") (pin "P23") (pinfunction "OUT23_P23") (pintype "bidirectional"))
      (node (ref "U$10") (pin "P24") (pinfunction "OUT24_P24") (pintype "bidirectional"))
      (node (ref "U$10") (pin "P6") (pinfunction "OUT6_P6") (pintype "bidirectional"))
      (node (ref "U$10") (pin "P7") (pinfunction "OUT7_P7") (pintype "bidirectional"))
      (node (ref "U$10") (pin "P8") (pinfunction "OUT8_P8") (pintype "bidirectional"))
      (node (ref "U$10") (pin "P9") (pinfunction "OUT9_P9") (pintype "bidirectional"))
      (node (ref "U$2") (pin "P$81") (pinfunction "ADCS2_VBAT_P$81") (pintype "bidirectional"))
      (node (ref "U$2") (pin "P$83") (pinfunction "ADCS2_VBAT_P$83") (pintype "bidirectional"))
    )
    (net (code "110") (name "VCC") (class "Default")
      (node (ref "C3") (pin "1") (pinfunction "1_1") (pintype "passive"))
      (node (ref "C4") (pin "1") (pinfunction "1_1") (pintype "passive"))
      (node (ref "C5") (pin "1") (pinfunction "1_1") (pintype "passive"))
      (node (ref "C6") (pin "1") (pinfunction "1_1") (pintype "passive"))
      (node (ref "C7") (pin "1") (pinfunction "1_1") (pintype "passive"))
      (node (ref "C8") (pin "1") (pinfunction "1_1") (pintype "passive"))
      (node (ref "C9") (pin "1") (pinfunction "1_1") (pintype "passive"))
      (node (ref "CIN2") (pin "1") (pinfunction "1_1") (pintype "passive"))
      (node (ref "CIN4") (pin "1") (pinfunction "1_1") (pintype "passive"))
      (node (ref "CV1") (pin "1") (pinfunction "1_1") (pintype "passive"))
      (node (ref "CV2") (pin "1") (pinfunction "1_1") (pintype "passive"))
      (node (ref "CV3") (pin "1") (pinfunction "1_1") (pintype "passive"))
      (node (ref "CV4") (pin "1") (pinfunction "1_1") (pintype "passive"))
      (node (ref "CV5") (pin "1") (pinfunction "1_1") (pintype "passive"))
      (node (ref "CV6") (pin "1") (pinfunction "1_1") (pintype "passive"))
      (node (ref "IC1") (pin "1") (pinfunction "IN_1") (pintype "input"))
      (node (ref "IC2") (pin "1") (pinfunction "IN_1") (pintype "input"))
      (node (ref "R_SENSE") (pin "1") (pinfunction "1_1") (pintype "passive"))
      (node (ref "R_SENSE3") (pin "1") (pinfunction "1_1") (pintype "passive"))
      (node (ref "R_SENSE4") (pin "1") (pinfunction "1_1") (pintype "passive"))
      (node (ref "R_SENSE5") (pin "1") (pinfunction "1_1") (pintype "passive"))
      (node (ref "R_SENSE6") (pin "1") (pinfunction "1_1") (pintype "passive"))
      (node (ref "R_SENSE7") (pin "1") (pinfunction "1_1") (pintype "passive"))
      (node (ref "R_SENSE8") (pin "1") (pinfunction "1_1") (pintype "passive"))
      (node (ref "R_SET") (pin "2") (pinfunction "2_2") (pintype "passive"))
      (node (ref "R_SET3") (pin "2") (pinfunction "2_2") (pintype "passive"))
      (node (ref "R_SET4") (pin "2") (pinfunction "2_2") (pintype "passive"))
      (node (ref "R_SET5") (pin "2") (pinfunction "2_2") (pintype "passive"))
      (node (ref "R_SET6") (pin "2") (pinfunction "2_2") (pintype "passive"))
      (node (ref "R_SET7") (pin "2") (pinfunction "2_2") (pintype "passive"))
      (node (ref "R_SET8") (pin "2") (pinfunction "2_2") (pintype "passive"))
      (node (ref "U$1") (pin "P29") (pinfunction "VCC_P29") (pintype "bidirectional"))
      (node (ref "U$10") (pin "P29") (pinfunction "VCC_P29") (pintype "bidirectional"))
      (node (ref "U$11") (pin "P29") (pinfunction "VCC_P29") (pintype "bidirectional"))
      (node (ref "U$12") (pin "P29") (pinfunction "VCC_P29") (pintype "bidirectional"))
      (node (ref "U$13") (pin "P$2") (pinfunction "VIN_P$2") (pintype "bidirectional"))
      (node (ref "U$14") (pin "P$2") (pinfunction "VIN_P$2") (pintype "bidirectional"))
      (node (ref "U$2") (pin "P$18") (pinfunction "DISTRI_VBAT_P$18") (pintype "bidirectional"))
      (node (ref "U$2") (pin "P$20") (pinfunction "DISTRI_VBAT_P$20") (pintype "bidirectional"))
      (node (ref "U$2") (pin "P$21") (pinfunction "DISTRI_VBAT_P$21") (pintype "bidirectional"))
      (node (ref "U$2") (pin "P$23") (pinfunction "DISTRI_VBAT_P$23") (pintype "bidirectional"))
      (node (ref "U$2") (pin "P$26") (pinfunction "DISTRI_VBAT_P$26") (pintype "bidirectional"))
      (node (ref "U$2") (pin "P$28") (pinfunction "DISTRI_VBAT_P$28") (pintype "bidirectional"))
      (node (ref "U$2") (pin "P$29") (pinfunction "DISTRI_VBAT_P$29") (pintype "bidirectional"))
      (node (ref "U$2") (pin "P$31") (pinfunction "DISTRI_VBAT_P$31") (pintype "bidirectional"))
      (node (ref "U$7") (pin "P29") (pinfunction "VCC_P29") (pintype "bidirectional"))
      (node (ref "U$8") (pin "P29") (pinfunction "VCC_P29") (pintype "bidirectional"))
      (node (ref "U$9") (pin "P29") (pinfunction "VCC_P29") (pintype "bidirectional"))
    )
    (net (code "111") (name "unconnected-(IC1-NC{slash}FB-Pad4)") (class "Default")
      (node (ref "IC1") (pin "4") (pinfunction "NC/FB_4") (pintype "passive"))
    )
    (net (code "112") (name "unconnected-(IC2-NC{slash}FB-Pad4)") (class "Default")
      (node (ref "IC2") (pin "4") (pinfunction "NC/FB_4") (pintype "passive"))
    )
    (net (code "113") (name "unconnected-(U$1-FLTB-PadP30)") (class "Default")
      (node (ref "U$1") (pin "P30") (pinfunction "FLTB_P30") (pintype "bidirectional"))
    )
    (net (code "114") (name "unconnected-(U$1-GATE-PadP25)") (class "Default")
      (node (ref "U$1") (pin "P25") (pinfunction "GATE_P25") (pintype "bidirectional"))
    )
    (net (code "115") (name "unconnected-(U$1-PGB-PadP31)") (class "Default")
      (node (ref "U$1") (pin "P31") (pinfunction "PGB_P31") (pintype "bidirectional"))
    )
    (net (code "116") (name "unconnected-(U$2-BDOT_I2C_SCL-PadP$90)") (class "Default")
      (node (ref "U$2") (pin "P$90") (pinfunction "BDOT_I2C_SCL_P$90") (pintype "bidirectional"))
    )
    (net (code "117") (name "unconnected-(U$2-BDOT_I2C_SDA-PadP$89)") (class "Default")
      (node (ref "U$2") (pin "P$89") (pinfunction "BDOT_I2C_SDA_P$89") (pintype "bidirectional"))
    )
    (net (code "118") (name "unconnected-(U$2-ESTIMAT_I2C_SCL-PadP$70)") (class "Default")
      (node (ref "U$2") (pin "P$70") (pinfunction "ESTIMAT_I2C_SCL_P$70") (pintype "bidirectional"))
    )
    (net (code "119") (name "unconnected-(U$2-ESTIMAT_I2C_SDA-PadP$69)") (class "Default")
      (node (ref "U$2") (pin "P$69") (pinfunction "ESTIMAT_I2C_SDA_P$69") (pintype "bidirectional"))
    )
    (net (code "120") (name "unconnected-(U$2-MAG1_PWM-PadP$73)") (class "Default")
      (node (ref "U$2") (pin "P$73") (pinfunction "MAG1_PWM_P$73") (pintype "bidirectional"))
    )
    (net (code "121") (name "unconnected-(U$2-MAG2_PWM-PadP$74)") (class "Default")
      (node (ref "U$2") (pin "P$74") (pinfunction "MAG2_PWM_P$74") (pintype "bidirectional"))
    )
    (net (code "122") (name "unconnected-(U$2-MAG3_PWM-PadP$75)") (class "Default")
      (node (ref "U$2") (pin "P$75") (pinfunction "MAG3_PWM_P$75") (pintype "bidirectional"))
    )
    (net (code "123") (name "unconnected-(U$2-PadP$33)") (class "Default")
      (node (ref "U$2") (pin "P$33") (pinfunction "P$33_P$33") (pintype "bidirectional"))
    )
    (net (code "124") (name "unconnected-(U$2-PadP$34)") (class "Default")
      (node (ref "U$2") (pin "P$34") (pinfunction "P$34_P$34") (pintype "bidirectional"))
    )
    (net (code "125") (name "unconnected-(U$2-PadP$35)") (class "Default")
      (node (ref "U$2") (pin "P$35") (pinfunction "P$35_P$35") (pintype "bidirectional"))
    )
    (net (code "126") (name "unconnected-(U$2-PadP$36)") (class "Default")
      (node (ref "U$2") (pin "P$36") (pinfunction "P$36_P$36") (pintype "bidirectional"))
    )
    (net (code "127") (name "unconnected-(U$2-PadP$37)") (class "Default")
      (node (ref "U$2") (pin "P$37") (pinfunction "P$37_P$37") (pintype "bidirectional"))
    )
    (net (code "128") (name "unconnected-(U$2-PadP$38)") (class "Default")
      (node (ref "U$2") (pin "P$38") (pinfunction "P$38_P$38") (pintype "bidirectional"))
    )
    (net (code "129") (name "unconnected-(U$2-PadP$39)") (class "Default")
      (node (ref "U$2") (pin "P$39") (pinfunction "P$39_P$39") (pintype "bidirectional"))
    )
    (net (code "130") (name "unconnected-(U$2-PadP$40)") (class "Default")
      (node (ref "U$2") (pin "P$40") (pinfunction "P$40_P$40") (pintype "bidirectional"))
    )
    (net (code "131") (name "unconnected-(U$2-PadP$41)") (class "Default")
      (node (ref "U$2") (pin "P$41") (pinfunction "P$41_P$41") (pintype "bidirectional"))
    )
    (net (code "132") (name "unconnected-(U$2-PadP$42)") (class "Default")
      (node (ref "U$2") (pin "P$42") (pinfunction "P$42_P$42") (pintype "bidirectional"))
    )
    (net (code "133") (name "unconnected-(U$2-PadP$43)") (class "Default")
      (node (ref "U$2") (pin "P$43") (pinfunction "P$43_P$43") (pintype "bidirectional"))
    )
    (net (code "134") (name "unconnected-(U$2-PadP$44)") (class "Default")
      (node (ref "U$2") (pin "P$44") (pinfunction "P$44_P$44") (pintype "bidirectional"))
    )
    (net (code "135") (name "unconnected-(U$2-PadP$48)") (class "Default")
      (node (ref "U$2") (pin "P$48") (pinfunction "P$48_P$48") (pintype "bidirectional"))
    )
    (net (code "136") (name "unconnected-(U$2-PadP$52)") (class "Default")
      (node (ref "U$2") (pin "P$52") (pinfunction "P$52_P$52") (pintype "bidirectional"))
    )
    (net (code "137") (name "unconnected-(U$2-PadP$56)") (class "Default")
      (node (ref "U$2") (pin "P$56") (pinfunction "P$56_P$56") (pintype "bidirectional"))
    )
    (net (code "138") (name "unconnected-(U$2-PadP$60)") (class "Default")
      (node (ref "U$2") (pin "P$60") (pinfunction "P$60_P$60") (pintype "bidirectional"))
    )
    (net (code "139") (name "unconnected-(U$2-PadP$61)") (class "Default")
      (node (ref "U$2") (pin "P$61") (pinfunction "P$61_P$61") (pintype "bidirectional"))
    )
    (net (code "140") (name "unconnected-(U$2-PadP$62)") (class "Default")
      (node (ref "U$2") (pin "P$62") (pinfunction "P$62_P$62") (pintype "bidirectional"))
    )
    (net (code "141") (name "unconnected-(U$2-PadP$63)") (class "Default")
      (node (ref "U$2") (pin "P$63") (pinfunction "P$63_P$63") (pintype "bidirectional"))
    )
    (net (code "142") (name "unconnected-(U$2-PadP$64)") (class "Default")
      (node (ref "U$2") (pin "P$64") (pinfunction "P$64_P$64") (pintype "bidirectional"))
    )
    (net (code "143") (name "unconnected-(U$2-PadP$65)") (class "Default")
      (node (ref "U$2") (pin "P$65") (pinfunction "P$65_P$65") (pintype "bidirectional"))
    )
    (net (code "144") (name "unconnected-(U$2-PadP$66)") (class "Default")
      (node (ref "U$2") (pin "P$66") (pinfunction "P$66_P$66") (pintype "bidirectional"))
    )
    (net (code "145") (name "unconnected-(U$2-PadP$67)") (class "Default")
      (node (ref "U$2") (pin "P$67") (pinfunction "P$67_P$67") (pintype "bidirectional"))
    )
    (net (code "146") (name "unconnected-(U$2-PadP$68)") (class "Default")
      (node (ref "U$2") (pin "P$68") (pinfunction "P$68_P$68") (pintype "bidirectional"))
    )
    (net (code "147") (name "unconnected-(U$2-PadP$71)") (class "Default")
      (node (ref "U$2") (pin "P$71") (pinfunction "P$71_P$71") (pintype "bidirectional"))
    )
    (net (code "148") (name "unconnected-(U$2-PadP$72)") (class "Default")
      (node (ref "U$2") (pin "P$72") (pinfunction "P$72_P$72") (pintype "bidirectional"))
    )
    (net (code "149") (name "unconnected-(U$2-PadP$76)") (class "Default")
      (node (ref "U$2") (pin "P$76") (pinfunction "P$76_P$76") (pintype "bidirectional"))
    )
    (net (code "150") (name "unconnected-(U$2-PadP$91)") (class "Default")
      (node (ref "U$2") (pin "P$91") (pinfunction "P$91_P$91") (pintype "bidirectional"))
    )
    (net (code "151") (name "unconnected-(U$2-PadP$92)") (class "Default")
      (node (ref "U$2") (pin "P$92") (pinfunction "P$92_P$92") (pintype "bidirectional"))
    )
    (net (code "152") (name "unconnected-(U$2-PadP$95)") (class "Default")
      (node (ref "U$2") (pin "P$95") (pinfunction "P$95_P$95") (pintype "bidirectional"))
    )
    (net (code "153") (name "unconnected-(U$2-PadP$96)") (class "Default")
      (node (ref "U$2") (pin "P$96") (pinfunction "P$96_P$96") (pintype "bidirectional"))
    )
    (net (code "154") (name "unconnected-(U$5-FLTB-PadP30)") (class "Default")
      (node (ref "U$5") (pin "P30") (pinfunction "FLTB_P30") (pintype "bidirectional"))
    )
    (net (code "155") (name "unconnected-(U$5-GATE-PadP25)") (class "Default")
      (node (ref "U$5") (pin "P25") (pinfunction "GATE_P25") (pintype "bidirectional"))
    )
    (net (code "156") (name "unconnected-(U$5-PGB-PadP31)") (class "Default")
      (node (ref "U$5") (pin "P31") (pinfunction "PGB_P31") (pintype "bidirectional"))
    )
    (net (code "157") (name "unconnected-(U$6-FLTB-PadP30)") (class "Default")
      (node (ref "U$6") (pin "P30") (pinfunction "FLTB_P30") (pintype "bidirectional"))
    )
    (net (code "158") (name "unconnected-(U$6-GATE-PadP25)") (class "Default")
      (node (ref "U$6") (pin "P25") (pinfunction "GATE_P25") (pintype "bidirectional"))
    )
    (net (code "159") (name "unconnected-(U$6-PGB-PadP31)") (class "Default")
      (node (ref "U$6") (pin "P31") (pinfunction "PGB_P31") (pintype "bidirectional"))
    )
    (net (code "160") (name "unconnected-(U$7-FLTB-PadP30)") (class "Default")
      (node (ref "U$7") (pin "P30") (pinfunction "FLTB_P30") (pintype "bidirectional"))
    )
    (net (code "161") (name "unconnected-(U$7-GATE-PadP25)") (class "Default")
      (node (ref "U$7") (pin "P25") (pinfunction "GATE_P25") (pintype "bidirectional"))
    )
    (net (code "162") (name "unconnected-(U$7-PGB-PadP31)") (class "Default")
      (node (ref "U$7") (pin "P31") (pinfunction "PGB_P31") (pintype "bidirectional"))
    )
    (net (code "163") (name "unconnected-(U$8-FLTB-PadP30)") (class "Default")
      (node (ref "U$8") (pin "P30") (pinfunction "FLTB_P30") (pintype "bidirectional"))
    )
    (net (code "164") (name "unconnected-(U$8-GATE-PadP25)") (class "Default")
      (node (ref "U$8") (pin "P25") (pinfunction "GATE_P25") (pintype "bidirectional"))
    )
    (net (code "165") (name "unconnected-(U$8-PGB-PadP31)") (class "Default")
      (node (ref "U$8") (pin "P31") (pinfunction "PGB_P31") (pintype "bidirectional"))
    )
    (net (code "166") (name "unconnected-(U$9-FLTB-PadP30)") (class "Default")
      (node (ref "U$9") (pin "P30") (pinfunction "FLTB_P30") (pintype "bidirectional"))
    )
    (net (code "167") (name "unconnected-(U$9-GATE-PadP25)") (class "Default")
      (node (ref "U$9") (pin "P25") (pinfunction "GATE_P25") (pintype "bidirectional"))
    )
    (net (code "168") (name "unconnected-(U$9-PGB-PadP31)") (class "Default")
      (node (ref "U$9") (pin "P31") (pinfunction "PGB_P31") (pintype "bidirectional"))
    )
    (net (code "169") (name "unconnected-(U$10-FLTB-PadP30)") (class "Default")
      (node (ref "U$10") (pin "P30") (pinfunction "FLTB_P30") (pintype "bidirectional"))
    )
    (net (code "170") (name "unconnected-(U$10-GATE-PadP25)") (class "Default")
      (node (ref "U$10") (pin "P25") (pinfunction "GATE_P25") (pintype "bidirectional"))
    )
    (net (code "171") (name "unconnected-(U$10-PGB-PadP31)") (class "Default")
      (node (ref "U$10") (pin "P31") (pinfunction "PGB_P31") (pintype "bidirectional"))
    )
    (net (code "172") (name "unconnected-(U$11-FLTB-PadP30)") (class "Default")
      (node (ref "U$11") (pin "P30") (pinfunction "FLTB_P30") (pintype "bidirectional"))
    )
    (net (code "173") (name "unconnected-(U$11-GATE-PadP25)") (class "Default")
      (node (ref "U$11") (pin "P25") (pinfunction "GATE_P25") (pintype "bidirectional"))
    )
    (net (code "174") (name "unconnected-(U$11-PGB-PadP31)") (class "Default")
      (node (ref "U$11") (pin "P31") (pinfunction "PGB_P31") (pintype "bidirectional"))
    )
    (net (code "175") (name "unconnected-(U$12-FLTB-PadP30)") (class "Default")
      (node (ref "U$12") (pin "P30") (pinfunction "FLTB_P30") (pintype "bidirectional"))
    )
    (net (code "176") (name "unconnected-(U$12-GATE-PadP25)") (class "Default")
      (node (ref "U$12") (pin "P25") (pinfunction "GATE_P25") (pintype "bidirectional"))
    )
    (net (code "177") (name "unconnected-(U$12-PGB-PadP31)") (class "Default")
      (node (ref "U$12") (pin "P31") (pinfunction "PGB_P31") (pintype "bidirectional"))
    )
    (net (code "178") (name "unconnected-(U$13-PGOOD-PadP$4)") (class "Default")
      (node (ref "U$13") (pin "P$4") (pinfunction "PGOOD_P$4") (pintype "bidirectional"))
    )
    (net (code "179") (name "unconnected-(U$14-PGOOD-PadP$4)") (class "Default")
      (node (ref "U$14") (pin "P$4") (pinfunction "PGOOD_P$4") (pintype "bidirectional"))
    )
    (net (code "180") (name "unconnected-(U$15-P2.3_SPI-CS2-PadP2.4_SPI-CS2)") (class "Default")
      (node (ref "U$15") (pin "P2.4_SPI-CS2") (pinfunction "P2.3_SPI-CS2_P2.4_SPI-CS2") (pintype "bidirectional"))
    )
    (net (code "181") (name "unconnected-(U$15-PadCANH)") (class "Default")
      (node (ref "U$15") (pin "CANH") (pinfunction "CANH_CANH") (pintype "bidirectional"))
    )
    (net (code "182") (name "unconnected-(U$15-PadCANL)") (class "Default")
      (node (ref "U$15") (pin "CANL") (pinfunction "CANL_CANL") (pintype "bidirectional"))
    )
    (net (code "183") (name "unconnected-(U$15-PadP1.5_A5)") (class "Default")
      (node (ref "U$15") (pin "P1.5_A5") (pinfunction "P1.5_A5_P1.5_A5") (pintype "bidirectional"))
    )
    (net (code "184") (name "unconnected-(U$15-PadP2.2_GPIO{slash}PWM)") (class "Default")
      (node (ref "U$15") (pin "P2.2_GPIO/PWM") (pinfunction "P2.2_GPIO/PWM_P2.2_GPIO/PWM") (pintype "bidirectional"))
    )
    (net (code "185") (name "unconnected-(U$15-PadP2.6_GPIO{slash}PWM)") (class "Default")
      (node (ref "U$15") (pin "P2.6_GPIO/PWM") (pinfunction "P2.6_GPIO/PWM_P2.6_GPIO/PWM") (pintype "bidirectional"))
    )
    (net (code "186") (name "unconnected-(U$15-PadP2.7_SPI-CS3)") (class "Default")
      (node (ref "U$15") (pin "P2.7_SPI-CS3") (pinfunction "P2.7_SPI-CS3_P2.7_SPI-CS3") (pintype "bidirectional"))
    )
    (net (code "187") (name "unconnected-(U$15-PadP5.0_I2C-SDA-1)") (class "Default")
      (node (ref "U$15") (pin "P5.0_I2C-SDA-1") (pinfunction "P5.0_I2C-SDA-1_P5.0_I2C-SDA-1") (pintype "bidirectional"))
    )
    (net (code "188") (name "unconnected-(U$15-PadP5.1_I2C-SCL-1)") (class "Default")
      (node (ref "U$15") (pin "P5.1_I2C-SCL-1") (pinfunction "P5.1_I2C-SCL-1_P5.1_I2C-SCL-1") (pintype "bidirectional"))
    )
    (net (code "189") (name "unconnected-(U$15-PadP5.4_SPI-MOSI)") (class "Default")
      (node (ref "U$15") (pin "P5.4_SPI-MOSI") (pinfunction "P5.4_SPI-MOSI_P5.4_SPI-MOSI") (pintype "bidirectional"))
    )
    (net (code "190") (name "unconnected-(U$15-PadP5.5_SPI-MISO)") (class "Default")
      (node (ref "U$15") (pin "P5.5_SPI-MISO") (pinfunction "P5.5_SPI-MISO_P5.5_SPI-MISO") (pintype "bidirectional"))
    )
    (net (code "191") (name "unconnected-(U$15-PadP5.6_SPI-CLK)") (class "Default")
      (node (ref "U$15") (pin "P5.6_SPI-CLK") (pinfunction "P5.6_SPI-CLK_P5.6_SPI-CLK") (pintype "bidirectional"))
    )
    (net (code "192") (name "unconnected-(U$15-PadP7.0_I2C-SDA-2)") (class "Default")
      (node (ref "U$15") (pin "P7.0_I2C-SDA-2") (pinfunction "P7.0_I2C-SDA-2_P7.0_I2C-SDA-2") (pintype "bidirectional"))
    )
    (net (code "193") (name "unconnected-(U$15-PadP7.1_I2C-SCL-2)") (class "Default")
      (node (ref "U$15") (pin "P7.1_I2C-SCL-2") (pinfunction "P7.1_I2C-SCL-2_P7.1_I2C-SCL-2") (pintype "bidirectional"))
    )
    (net (code "194") (name "unconnected-(U$15-PadP7.2_SYNC1)") (class "Default")
      (node (ref "U$15") (pin "P7.2_SYNC1") (pinfunction "P7.2_SYNC1_P7.2_SYNC1") (pintype "bidirectional"))
    )
    (net (code "195") (name "unconnected-(U$15-PadPJ.3_SYNC2)") (class "Default")
      (node (ref "U$15") (pin "PJ.3_SYNC2") (pinfunction "PJ.3_SYNC2_PJ.3_SYNC2") (pintype "bidirectional"))
    )
  )
)
